# lupa-carrier.net
KiCad netlist of a schematic drawn in EAGLE
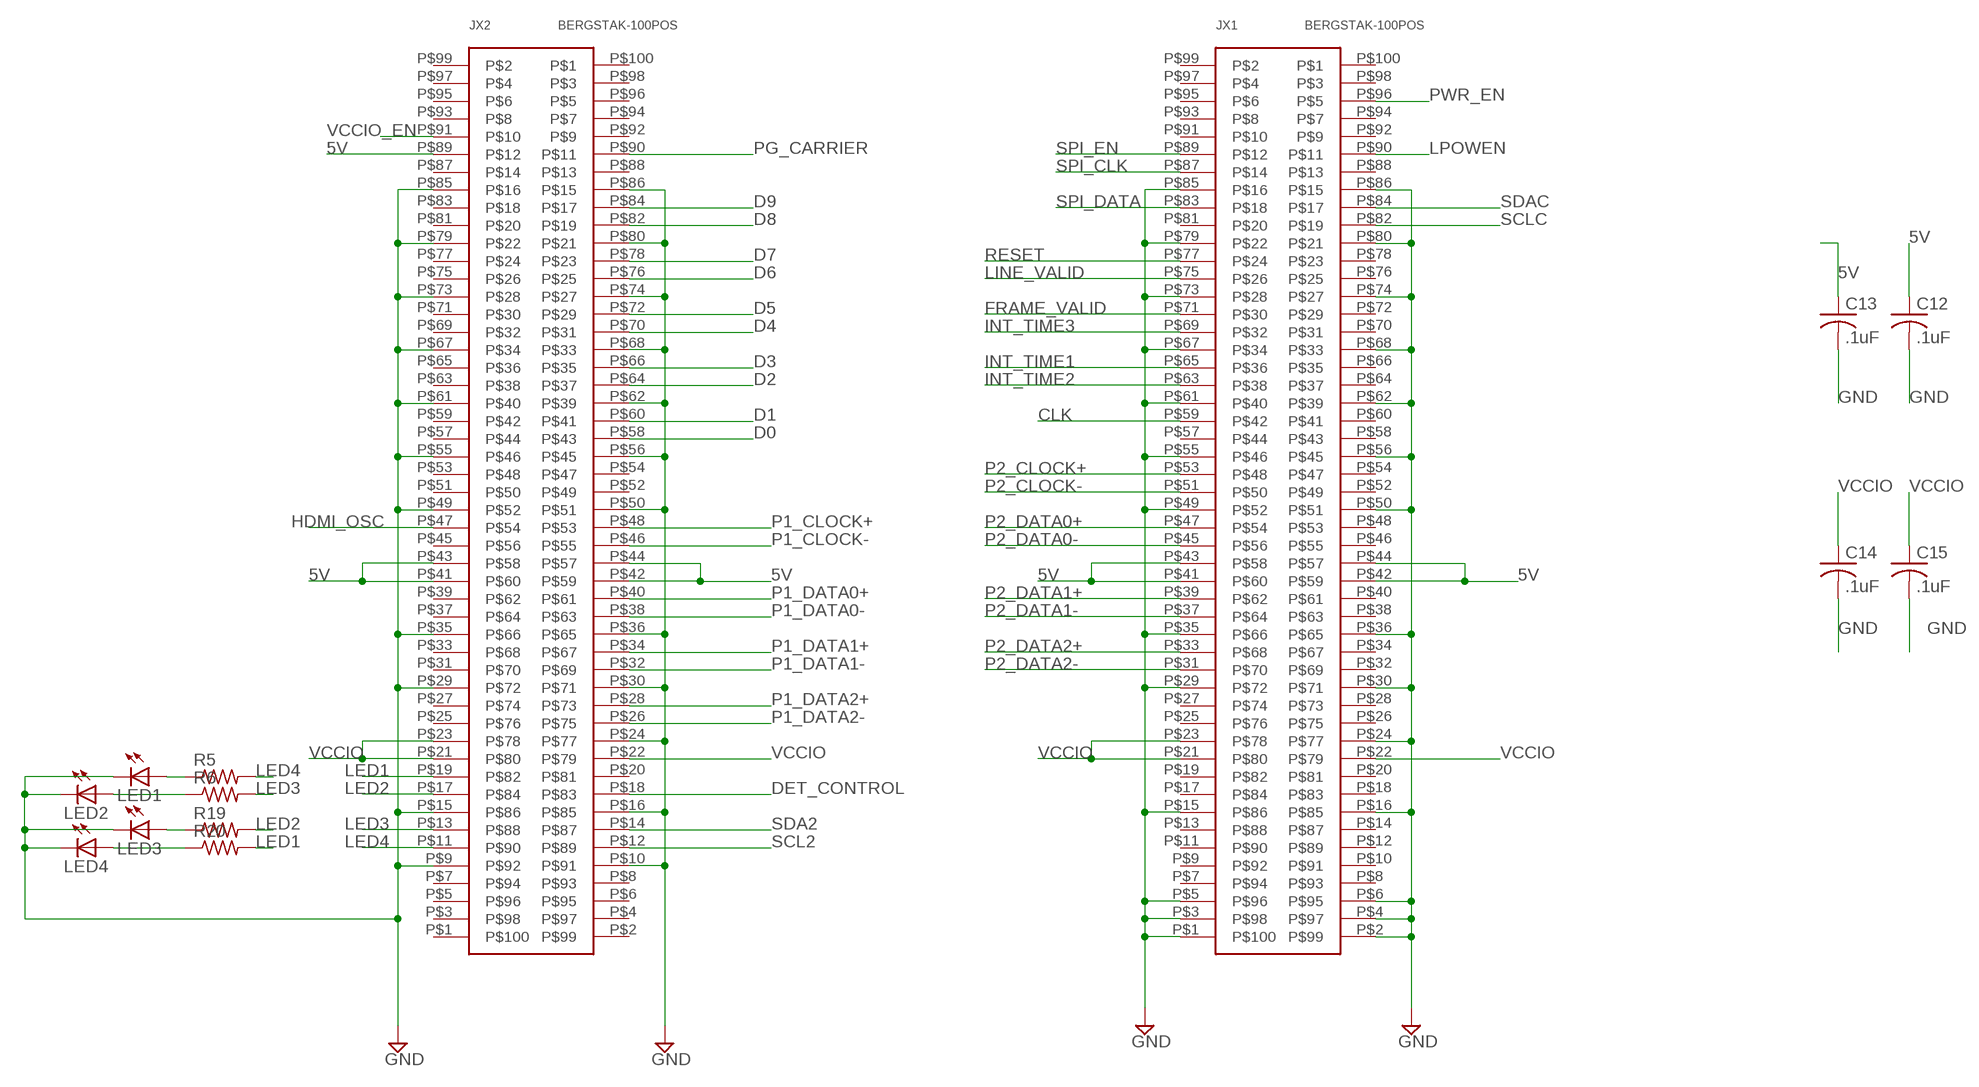
[diagram p0: schematic, sheet 1]
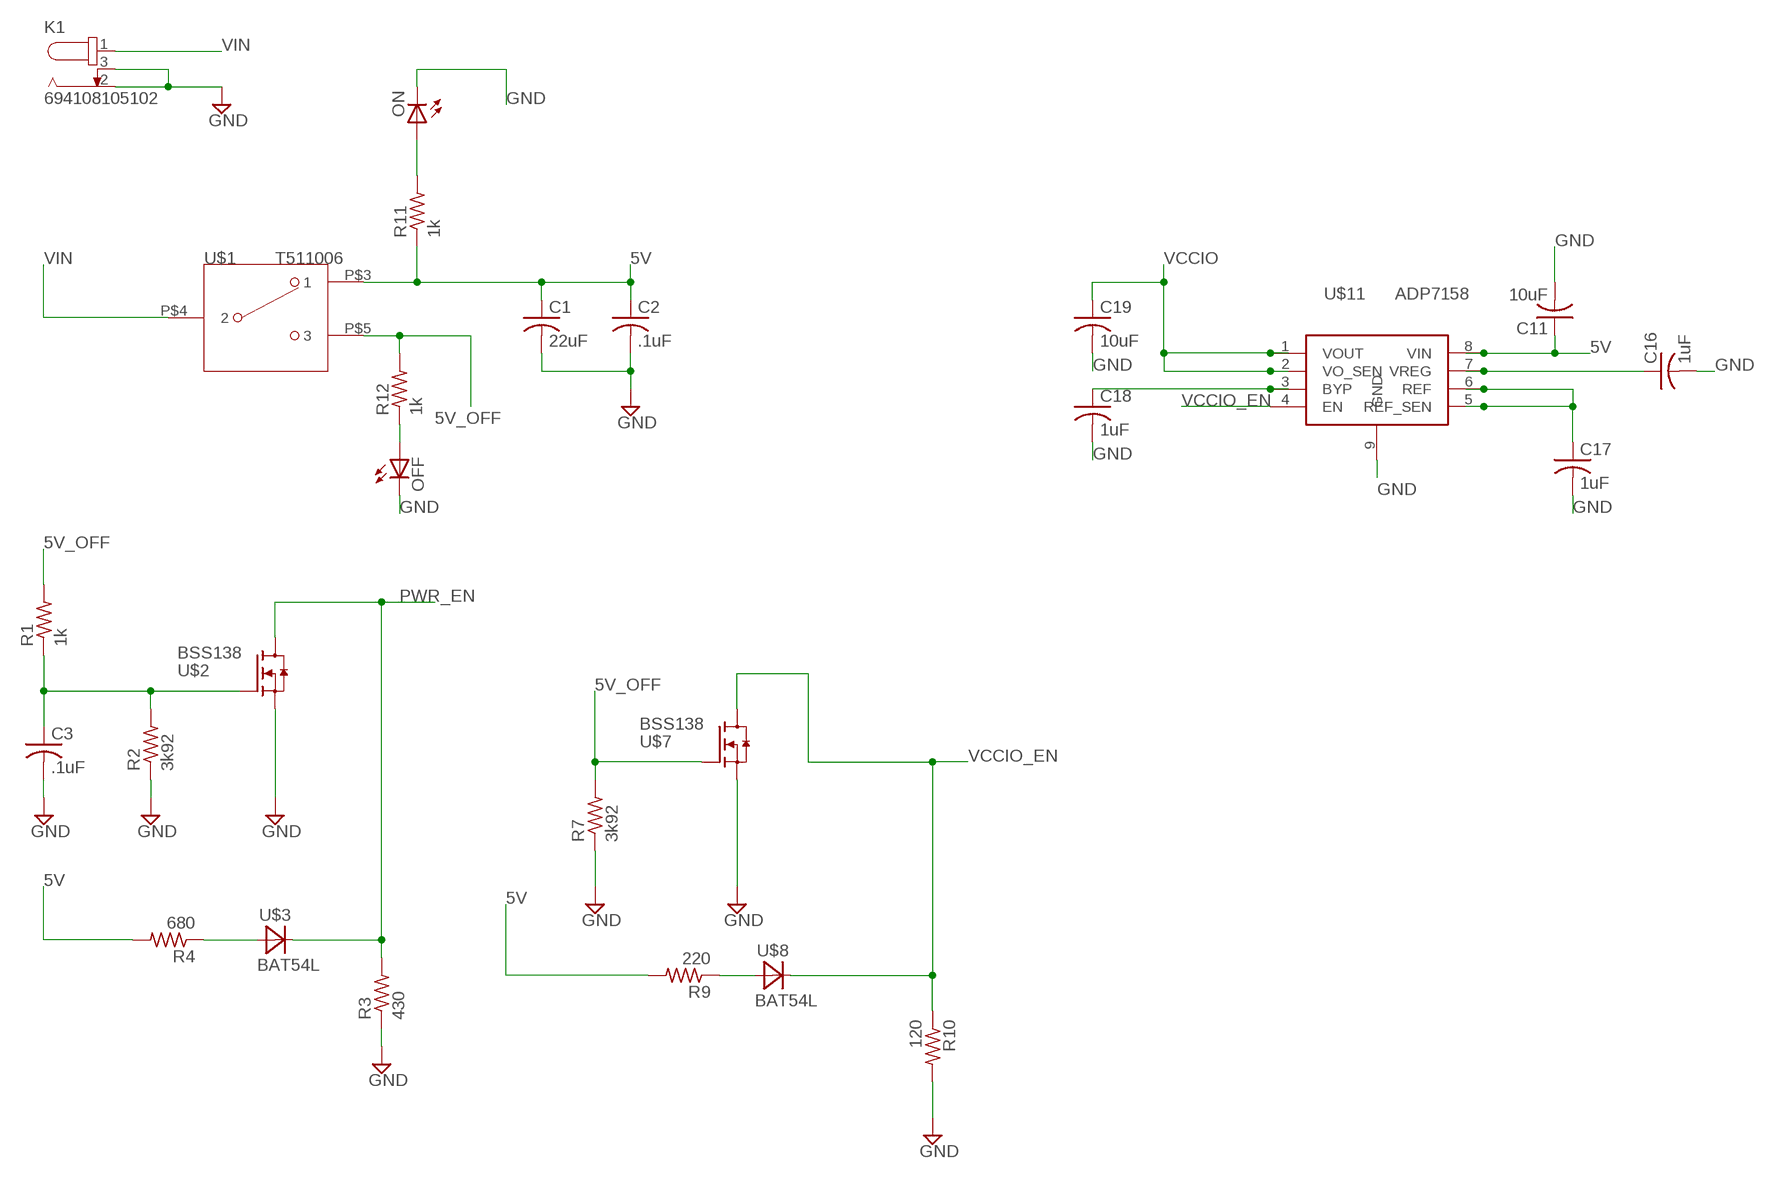
[diagram p1: schematic, sheet 2]
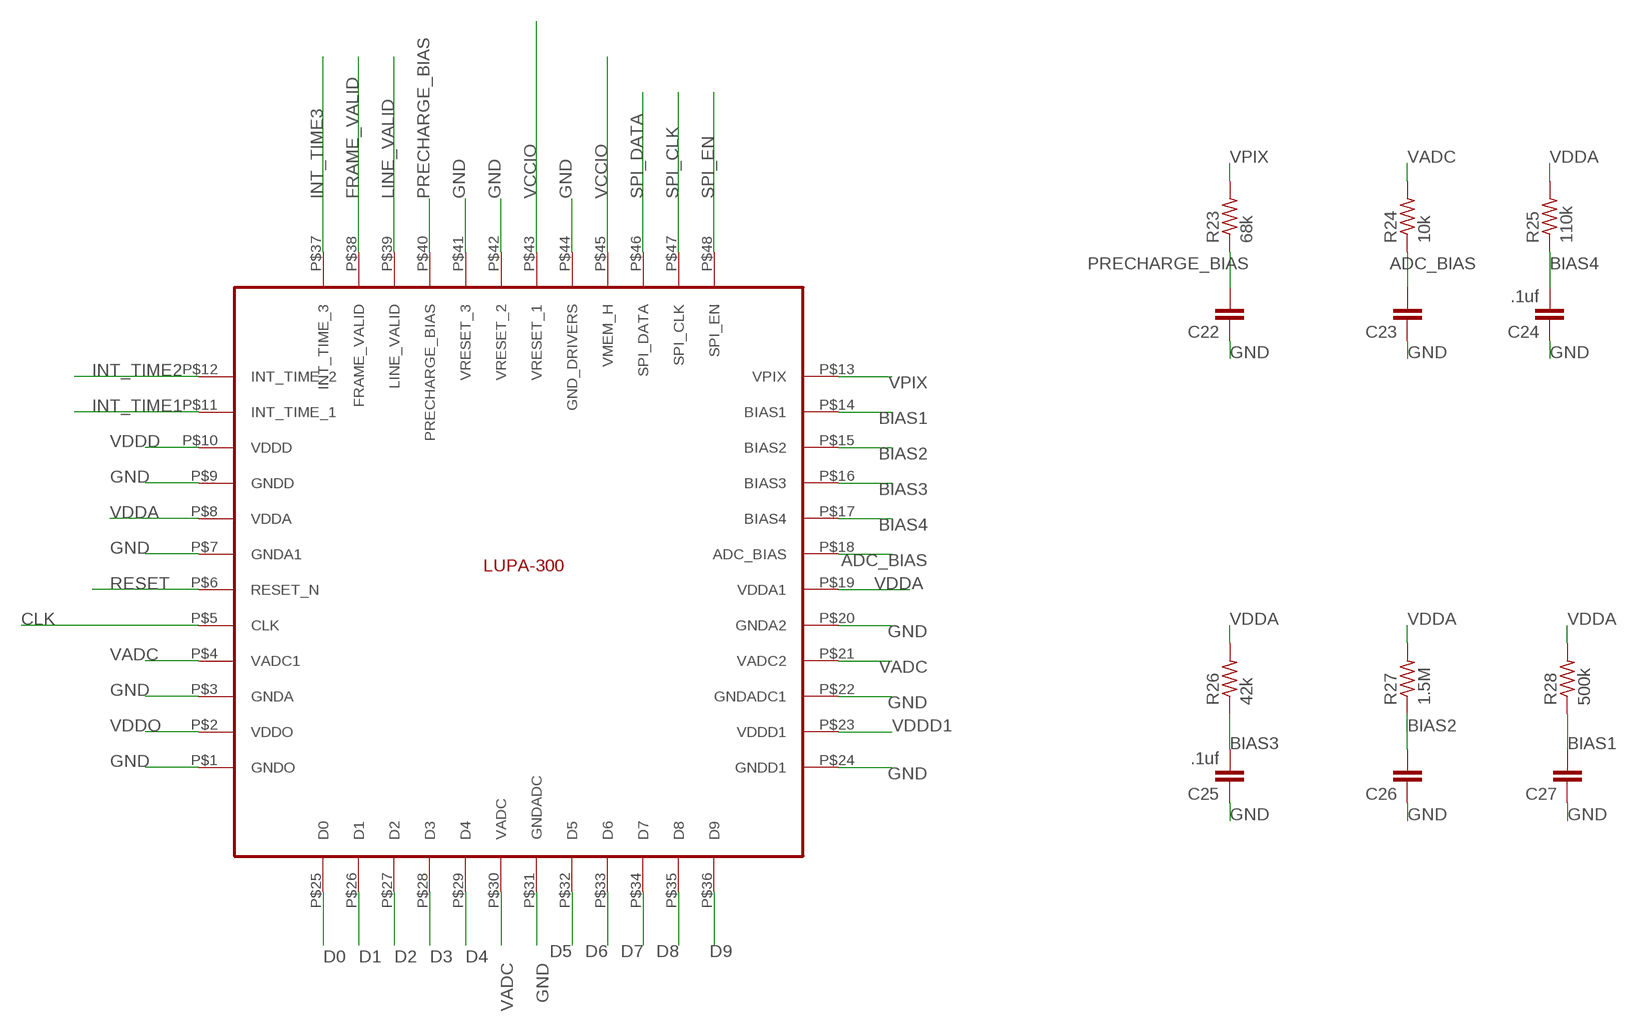
[diagram p2: schematic, sheet 3]
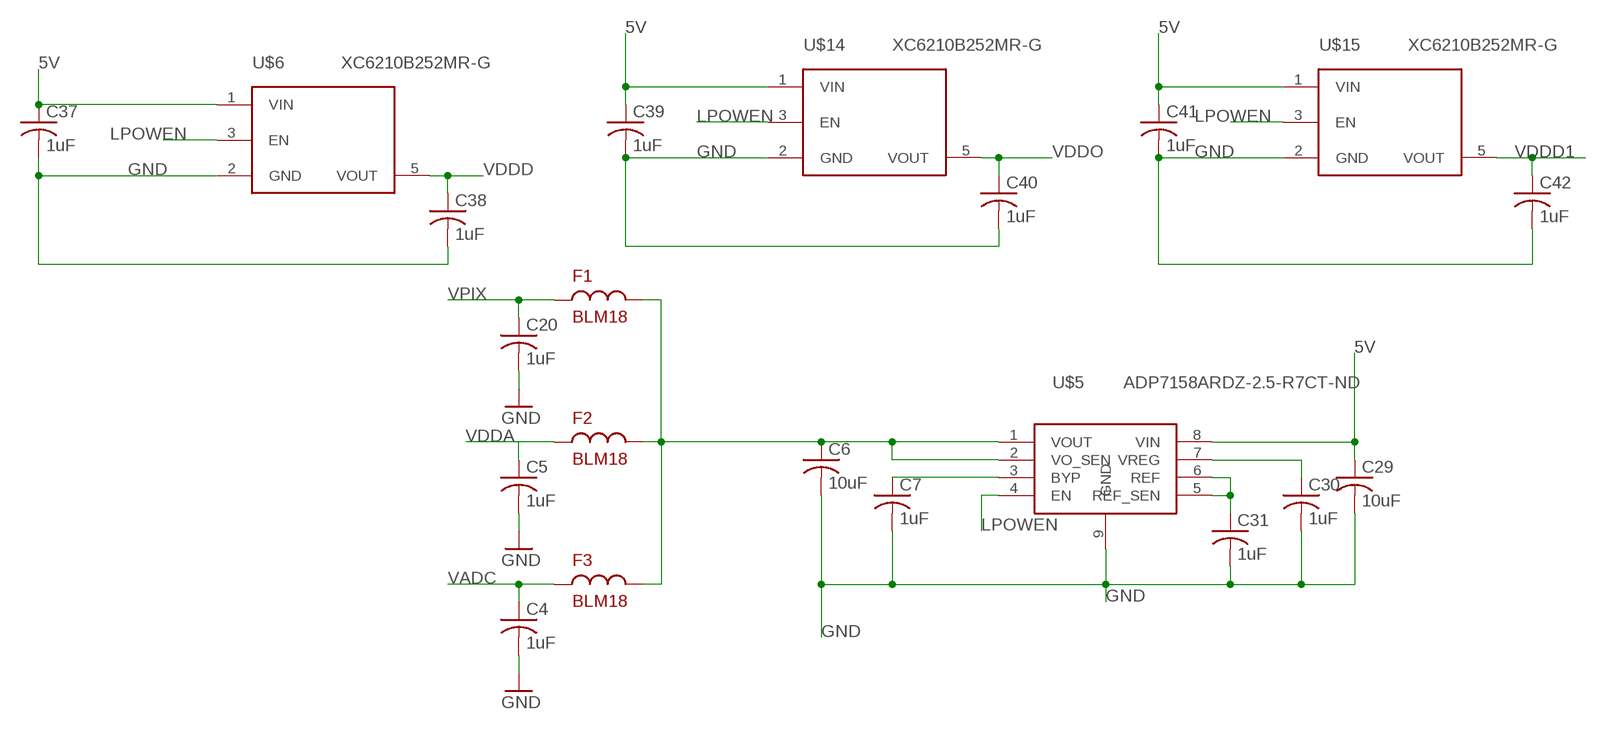
[diagram p3: schematic, sheet 4]
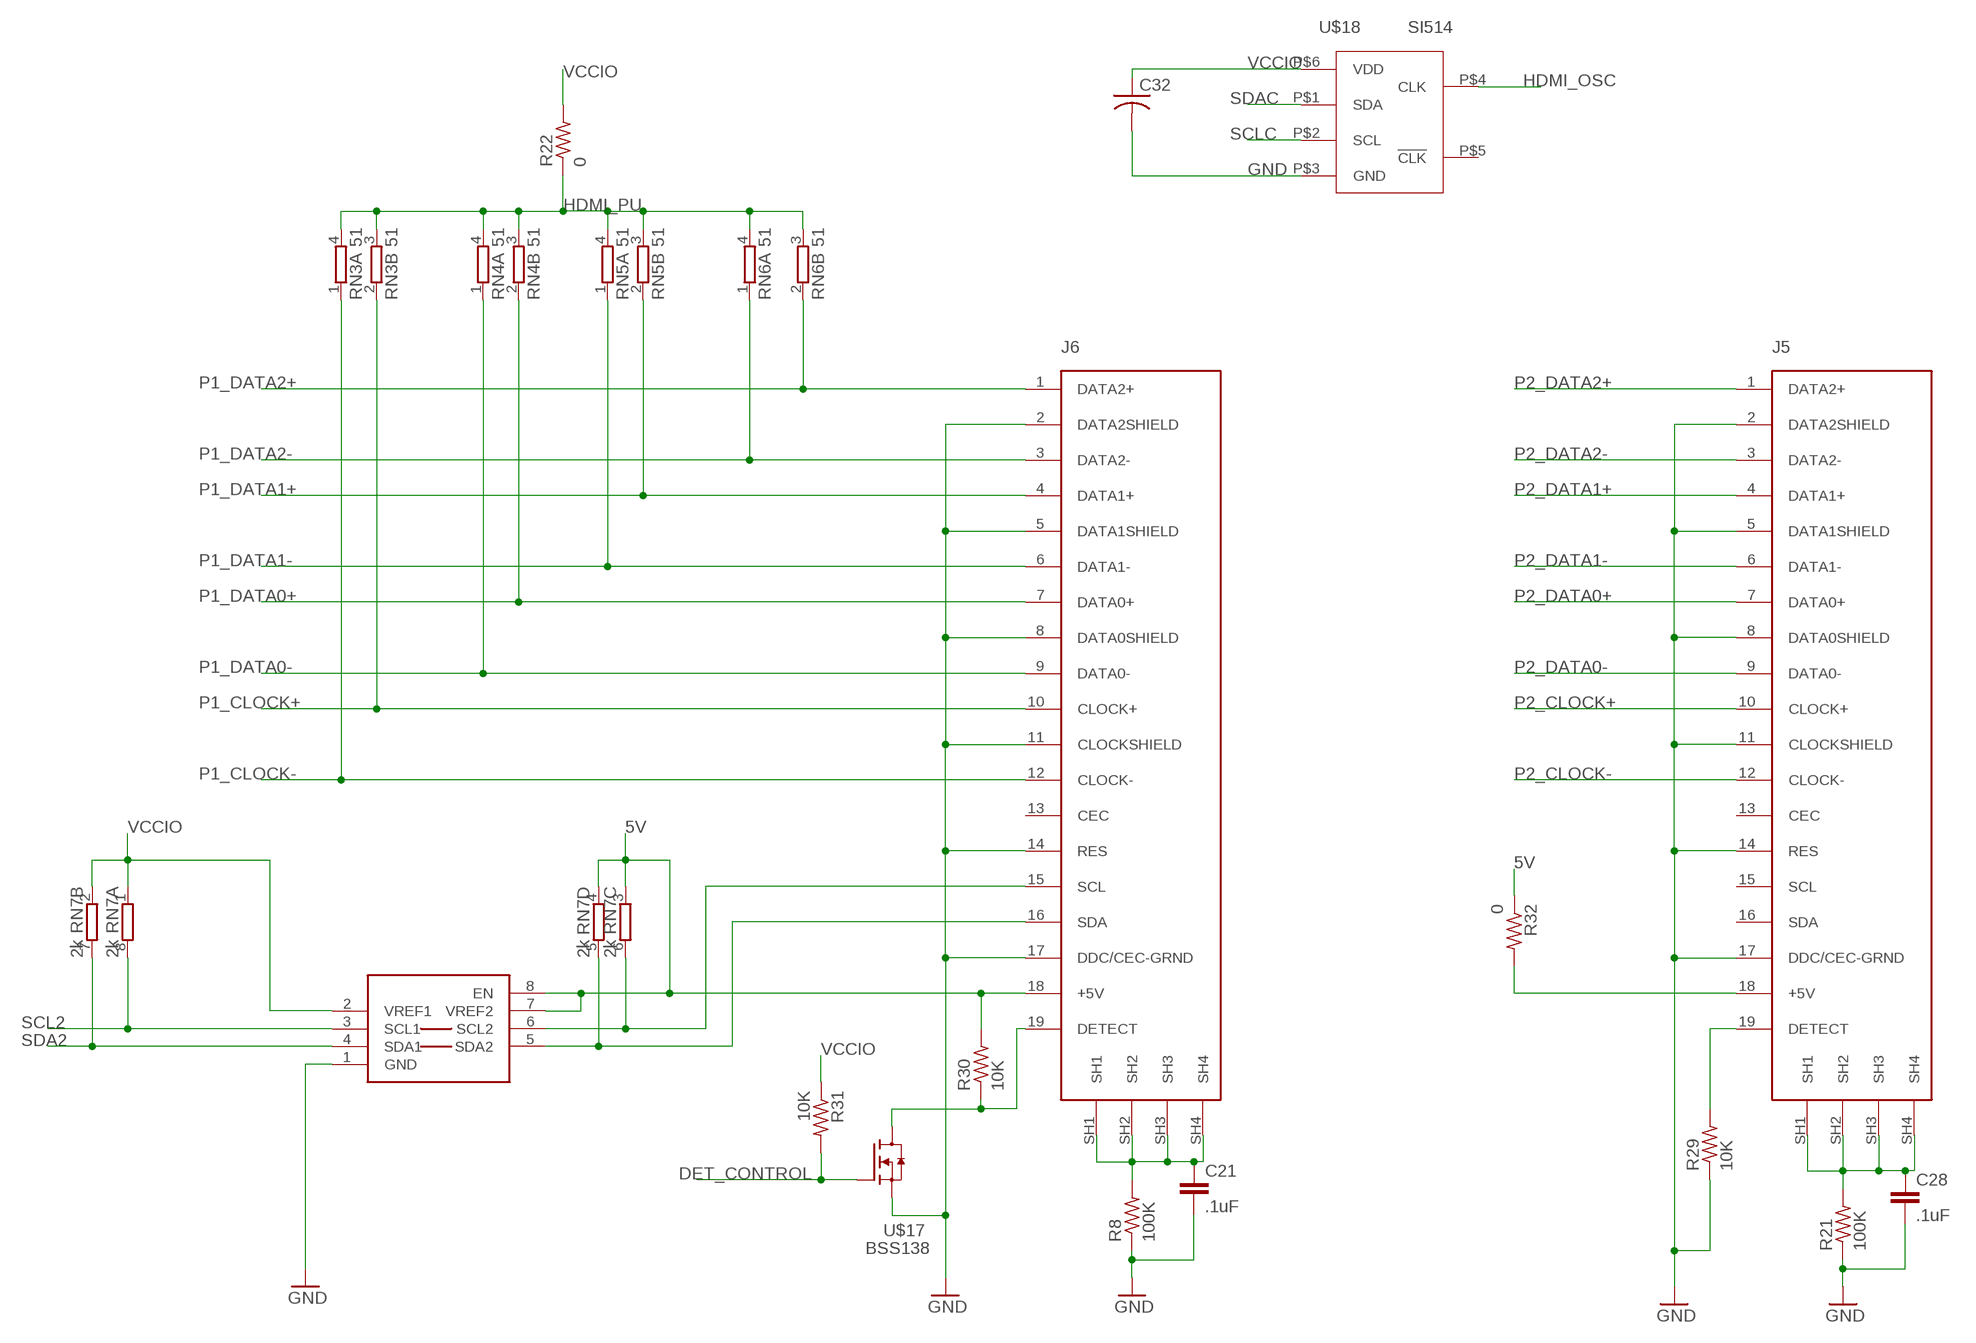
[diagram p4: schematic, sheet 5]

(export (version "E")
  (design (tool "Eeschema 10.0.6"))
  (components
    (comp (ref "C1")
      (value "22uF")
      (footprint "eagle-import:C1206")
      (libsource (lib "eagle-import") (part "C-USC1206"))
    )
    (comp (ref "C2")
      (value ".1uF")
      (footprint "eagle-import:C0603")
      (libsource (lib "eagle-import") (part "C-USC0603"))
    )
    (comp (ref "C3")
      (value ".1uF")
      (footprint "eagle-import:C0603")
      (libsource (lib "eagle-import") (part "C-USC0603"))
    )
    (comp (ref "C11")
      (value "10uF")
      (footprint "eagle-import:C0603")
      (libsource (lib "eagle-import") (part "C-USC0603"))
    )
    (comp (ref "C16")
      (value "1uF")
      (footprint "eagle-import:C0603")
      (libsource (lib "eagle-import") (part "C-USC0603"))
    )
    (comp (ref "C17")
      (value "1uF")
      (footprint "eagle-import:C0603")
      (libsource (lib "eagle-import") (part "C-USC0603"))
    )
    (comp (ref "C18")
      (value "1uF")
      (footprint "eagle-import:C0603")
      (libsource (lib "eagle-import") (part "C-USC0603"))
    )
    (comp (ref "C19")
      (value "10uF")
      (footprint "eagle-import:C0603")
      (libsource (lib "eagle-import") (part "C-USC0603"))
    )
    (comp (ref "K1")
      (value "694108105102")
      (footprint "eagle-import:694108105102")
      (libsource (lib "eagle-import") (part "694108105102"))
    )
    (comp (ref "OFF")
      (value "LEDCHIPLED_0805")
      (footprint "eagle-import:CHIPLED_0805")
      (libsource (lib "eagle-import") (part "LEDCHIPLED_0805"))
    )
    (comp (ref "ON")
      (value "LEDCHIPLED_0805")
      (footprint "eagle-import:CHIPLED_0805")
      (libsource (lib "eagle-import") (part "LEDCHIPLED_0805"))
    )
    (comp (ref "R1")
      (value "1k")
      (footprint "eagle-import:R0603")
      (libsource (lib "eagle-import") (part "rcl_334_R-US_R0603"))
    )
    (comp (ref "R2")
      (value "3k92")
      (footprint "eagle-import:R0603")
      (libsource (lib "eagle-import") (part "rcl_334_R-US_R0603"))
    )
    (comp (ref "R3")
      (value "430")
      (footprint "eagle-import:R0603")
      (libsource (lib "eagle-import") (part "rcl_334_R-US_R0603"))
    )
    (comp (ref "R4")
      (value "680")
      (footprint "eagle-import:R0603")
      (libsource (lib "eagle-import") (part "rcl_334_R-US_R0603"))
    )
    (comp (ref "R7")
      (value "3k92")
      (footprint "eagle-import:R0603")
      (libsource (lib "eagle-import") (part "rcl_334_R-US_R0603"))
    )
    (comp (ref "R9")
      (value "220")
      (footprint "eagle-import:R0603")
      (libsource (lib "eagle-import") (part "rcl_334_R-US_R0603"))
    )
    (comp (ref "R10")
      (value "120")
      (footprint "eagle-import:R0603")
      (libsource (lib "eagle-import") (part "rcl_334_R-US_R0603"))
    )
    (comp (ref "R11")
      (value "1k")
      (footprint "eagle-import:R0603")
      (libsource (lib "eagle-import") (part "rcl_334_R-US_R0603"))
    )
    (comp (ref "R12")
      (value "1k")
      (footprint "eagle-import:R0603")
      (libsource (lib "eagle-import") (part "rcl_334_R-US_R0603"))
    )
    (comp (ref "U$1")
      (value "T511006")
      (footprint "eagle-import:SPDT")
      (libsource (lib "eagle-import") (part "T511006"))
    )
    (comp (ref "U$2")
      (value "BSS138")
      (footprint "eagle-import:SOT23")
      (libsource (lib "eagle-import") (part "BSS138"))
    )
    (comp (ref "U$3")
      (value "BAT54L")
      (footprint "eagle-import:SOT23")
      (libsource (lib "eagle-import") (part "BAT54L"))
    )
    (comp (ref "U$7")
      (value "BSS138")
      (footprint "eagle-import:SOT23")
      (libsource (lib "eagle-import") (part "BSS138"))
    )
    (comp (ref "U$8")
      (value "BAT54L")
      (footprint "eagle-import:SOT23")
      (libsource (lib "eagle-import") (part "BAT54L"))
    )
    (comp (ref "U$11")
      (value "ADP7158")
      (footprint "eagle-import:SO08")
      (libsource (lib "eagle-import") (part "ADP7158"))
    )
    (comp (ref "C22")
      (value "C-EUC0603")
      (footprint "eagle-import:C0603")
      (libsource (lib "eagle-import") (part "rcl_334_C-EUC0603"))
    )
    (comp (ref "C23")
      (value "C-EUC0603")
      (footprint "eagle-import:C0603")
      (libsource (lib "eagle-import") (part "rcl_334_C-EUC0603"))
    )
    (comp (ref "C24")
      (value ".1uf")
      (footprint "eagle-import:C0603")
      (libsource (lib "eagle-import") (part "rcl_334_C-EUC0603"))
    )
    (comp (ref "C25")
      (value ".1uf")
      (footprint "eagle-import:C0603")
      (libsource (lib "eagle-import") (part "rcl_334_C-EUC0603"))
    )
    (comp (ref "C26")
      (value "C-EUC0603")
      (footprint "eagle-import:C0603")
      (libsource (lib "eagle-import") (part "rcl_334_C-EUC0603"))
    )
    (comp (ref "C27")
      (value "C-EUC0603")
      (footprint "eagle-import:C0603")
      (libsource (lib "eagle-import") (part "rcl_334_C-EUC0603"))
    )
    (comp (ref "R23")
      (value "68k")
      (footprint "eagle-import:R0603")
      (libsource (lib "eagle-import") (part "rcl_334_R-US_R0603"))
    )
    (comp (ref "R24")
      (value "10k")
      (footprint "eagle-import:R0603")
      (libsource (lib "eagle-import") (part "rcl_334_R-US_R0603"))
    )
    (comp (ref "R25")
      (value "110k")
      (footprint "eagle-import:R0603")
      (libsource (lib "eagle-import") (part "rcl_334_R-US_R0603"))
    )
    (comp (ref "R26")
      (value "42k")
      (footprint "eagle-import:R0603")
      (libsource (lib "eagle-import") (part "rcl_334_R-US_R0603"))
    )
    (comp (ref "R27")
      (value "1.5M")
      (footprint "eagle-import:R0603")
      (libsource (lib "eagle-import") (part "rcl_334_R-US_R0603"))
    )
    (comp (ref "R28")
      (value "500k")
      (footprint "eagle-import:R0603")
      (libsource (lib "eagle-import") (part "rcl_334_R-US_R0603"))
    )
    (comp (ref "U$4")
      (value "LUPA300")
      (footprint "eagle-import:LUPA300")
      (libsource (lib "eagle-import") (part "LUPA300"))
    )
    (comp (ref "C21")
      (value ".1uF")
      (footprint "eagle-import:C0603K")
      (libsource (lib "eagle-import") (part "C-EUC0603K"))
    )
    (comp (ref "C28")
      (value ".1uF")
      (footprint "eagle-import:C0603K")
      (libsource (lib "eagle-import") (part "C-EUC0603K"))
    )
    (comp (ref "C32")
      (value "C-USC0603")
      (footprint "eagle-import:C0603")
      (libsource (lib "eagle-import") (part "C-USC0603"))
    )
    (comp (ref "J5")
      (value "HDMI-TYPE-A-RECEPTICALFCI10029449")
      (footprint "eagle-import:FCI-HDMI-TYPE-A-RECEPT")
      (libsource (lib "eagle-import") (part "HDMI-TYPE-A-RECEPTICALFCI10029449"))
    )
    (comp (ref "J6")
      (value "HDMI-TYPE-A-RECEPTICALFCI10029449")
      (footprint "eagle-import:FCI-HDMI-TYPE-A-RECEPT")
      (libsource (lib "eagle-import") (part "HDMI-TYPE-A-RECEPTICALFCI10029449"))
    )
    (comp (ref "PCA9306")
      (value "PCA9306")
      (footprint "eagle-import:PSOP-8")
      (libsource (lib "eagle-import") (part "PCA9306"))
    )
    (comp (ref "R8")
      (value "100K")
      (footprint "eagle-import:R0603")
      (libsource (lib "eagle-import") (part "R-US_R0603"))
    )
    (comp (ref "R21")
      (value "100K")
      (footprint "eagle-import:R0603")
      (libsource (lib "eagle-import") (part "R-US_R0603"))
    )
    (comp (ref "R22")
      (value "0")
      (footprint "eagle-import:R0603")
      (libsource (lib "eagle-import") (part "rcl_334_R-US_R0603"))
    )
    (comp (ref "R29")
      (value "10K")
      (footprint "eagle-import:R0603")
      (libsource (lib "eagle-import") (part "R-US_R0603"))
    )
    (comp (ref "R30")
      (value "10K")
      (footprint "eagle-import:R0603")
      (libsource (lib "eagle-import") (part "R-US_R0603"))
    )
    (comp (ref "R31")
      (value "10K")
      (footprint "eagle-import:R0603")
      (libsource (lib "eagle-import") (part "R-US_R0603"))
    )
    (comp (ref "R32")
      (value "0")
      (footprint "eagle-import:R0603")
      (libsource (lib "eagle-import") (part "R-US_R0603"))
    )
    (comp (ref "RN3")
      (value "51")
      (footprint "eagle-import:EXB34V")
      (libsource (lib "eagle-import") (part "2R-NEXB34V"))
    )
    (comp (ref "RN4")
      (value "51")
      (footprint "eagle-import:EXB34V")
      (libsource (lib "eagle-import") (part "2R-NEXB34V"))
    )
    (comp (ref "RN5")
      (value "51")
      (footprint "eagle-import:EXB34V")
      (libsource (lib "eagle-import") (part "2R-NEXB34V"))
    )
    (comp (ref "RN6")
      (value "51")
      (footprint "eagle-import:EXB34V")
      (libsource (lib "eagle-import") (part "2R-NEXB34V"))
    )
    (comp (ref "RN7")
      (value "2k")
      (footprint "eagle-import:0603-ARV")
      (libsource (lib "eagle-import") (part "4R-N0603-ARV"))
    )
    (comp (ref "U$17")
      (value "BSS138")
      (footprint "eagle-import:SOT23")
      (libsource (lib "eagle-import") (part "BSS138"))
    )
    (comp (ref "U$18")
      (value "SI514")
      (footprint "eagle-import:XTAL-6PIN")
      (libsource (lib "eagle-import") (part "SI514"))
    )
    (comp (ref "C12")
      (value ".1uF")
      (footprint "eagle-import:C0603")
      (libsource (lib "eagle-import") (part "C-USC0603"))
    )
    (comp (ref "C13")
      (value ".1uF")
      (footprint "eagle-import:C0603")
      (libsource (lib "eagle-import") (part "C-USC0603"))
    )
    (comp (ref "C14")
      (value ".1uF")
      (footprint "eagle-import:C0603")
      (libsource (lib "eagle-import") (part "C-USC0603"))
    )
    (comp (ref "C15")
      (value ".1uF")
      (footprint "eagle-import:C0603")
      (libsource (lib "eagle-import") (part "C-USC0603"))
    )
    (comp (ref "JX1")
      (value "BERGSTAK-100POS")
      (footprint "eagle-import:BERG100POS")
      (libsource (lib "eagle-import") (part "BERGSTAK-100POS"))
    )
    (comp (ref "JX2")
      (value "BERGSTAK-100POS")
      (footprint "eagle-import:BERG100POS")
      (libsource (lib "eagle-import") (part "BERGSTAK-100POS"))
    )
    (comp (ref "LED1")
      (value "LEDCHIPLED_0805")
      (footprint "eagle-import:CHIPLED_0805")
      (libsource (lib "eagle-import") (part "led_259_LEDCHIPLED_0805"))
    )
    (comp (ref "LED2")
      (value "LEDCHIPLED_0805")
      (footprint "eagle-import:CHIPLED_0805")
      (libsource (lib "eagle-import") (part "led_259_LEDCHIPLED_0805"))
    )
    (comp (ref "LED3")
      (value "LEDCHIPLED_0805")
      (footprint "eagle-import:CHIPLED_0805")
      (libsource (lib "eagle-import") (part "led_259_LEDCHIPLED_0805"))
    )
    (comp (ref "LED4")
      (value "LEDCHIPLED_0805")
      (footprint "eagle-import:CHIPLED_0805")
      (libsource (lib "eagle-import") (part "led_259_LEDCHIPLED_0805"))
    )
    (comp (ref "R5")
      (value "R-US_R0603")
      (footprint "eagle-import:R0603")
      (libsource (lib "eagle-import") (part "resistor_348_R-US_R0603"))
    )
    (comp (ref "R6")
      (value "R-US_R0603")
      (footprint "eagle-import:R0603")
      (libsource (lib "eagle-import") (part "resistor_348_R-US_R0603"))
    )
    (comp (ref "R19")
      (value "R-US_R0603")
      (footprint "eagle-import:R0603")
      (libsource (lib "eagle-import") (part "resistor_348_R-US_R0603"))
    )
    (comp (ref "R20")
      (value "R-US_R0603")
      (footprint "eagle-import:R0603")
      (libsource (lib "eagle-import") (part "resistor_348_R-US_R0603"))
    )
    (comp (ref "C4")
      (value "1uF")
      (footprint "eagle-import:C0603")
      (libsource (lib "eagle-import") (part "C-USC0603"))
    )
    (comp (ref "C5")
      (value "1uF")
      (footprint "eagle-import:C0603")
      (libsource (lib "eagle-import") (part "C-USC0603"))
    )
    (comp (ref "C6")
      (value "10uF")
      (footprint "eagle-import:C0603")
      (libsource (lib "eagle-import") (part "C-USC0603"))
    )
    (comp (ref "C7")
      (value "1uF")
      (footprint "eagle-import:C0603")
      (libsource (lib "eagle-import") (part "C-USC0603"))
    )
    (comp (ref "C20")
      (value "1uF")
      (footprint "eagle-import:C0603")
      (libsource (lib "eagle-import") (part "C-USC0603"))
    )
    (comp (ref "C29")
      (value "10uF")
      (footprint "eagle-import:C0603")
      (libsource (lib "eagle-import") (part "C-USC0603"))
    )
    (comp (ref "C30")
      (value "1uF")
      (footprint "eagle-import:C0603")
      (libsource (lib "eagle-import") (part "C-USC0603"))
    )
    (comp (ref "C31")
      (value "1uF")
      (footprint "eagle-import:C0603")
      (libsource (lib "eagle-import") (part "C-USC0603"))
    )
    (comp (ref "C37")
      (value "1uF")
      (footprint "eagle-import:C0603")
      (libsource (lib "eagle-import") (part "C-USC0603"))
    )
    (comp (ref "C38")
      (value "1uF")
      (footprint "eagle-import:C0603")
      (libsource (lib "eagle-import") (part "C-USC0603"))
    )
    (comp (ref "C39")
      (value "1uF")
      (footprint "eagle-import:C0603")
      (libsource (lib "eagle-import") (part "C-USC0603"))
    )
    (comp (ref "C40")
      (value "1uF")
      (footprint "eagle-import:C0603")
      (libsource (lib "eagle-import") (part "C-USC0603"))
    )
    (comp (ref "C41")
      (value "1uF")
      (footprint "eagle-import:C0603")
      (libsource (lib "eagle-import") (part "C-USC0603"))
    )
    (comp (ref "C42")
      (value "1uF")
      (footprint "eagle-import:C0603")
      (libsource (lib "eagle-import") (part "C-USC0603"))
    )
    (comp (ref "F1")
      (value "BLM18")
      (footprint "eagle-import:C0603K")
      (libsource (lib "eagle-import") (part "BLM18"))
    )
    (comp (ref "F2")
      (value "BLM18")
      (footprint "eagle-import:C0603K")
      (libsource (lib "eagle-import") (part "BLM18"))
    )
    (comp (ref "F3")
      (value "BLM18")
      (footprint "eagle-import:C0603K")
      (libsource (lib "eagle-import") (part "BLM18"))
    )
    (comp (ref "U$5")
      (value "ADP7158ARDZ-2.5-R7CT-ND")
      (footprint "eagle-import:SO08")
      (libsource (lib "eagle-import") (part "ADP7158ARDZ-2.5-R7CT-ND"))
    )
    (comp (ref "U$6")
      (value "XC6210B252MR-G")
      (footprint "eagle-import:SOT25")
      (libsource (lib "eagle-import") (part "XC6210B252MR-G"))
    )
    (comp (ref "U$14")
      (value "XC6210B252MR-G")
      (footprint "eagle-import:SOT25")
      (libsource (lib "eagle-import") (part "XC6210B252MR-G"))
    )
    (comp (ref "U$15")
      (value "XC6210B252MR-G")
      (footprint "eagle-import:SOT25")
      (libsource (lib "eagle-import") (part "XC6210B252MR-G"))
    )
  )
  (nets
    (net (code "1") (name "5V") (class "Default")
      (node (ref "C1") (pin "1") (pinfunction "1_1") (pintype "passive"))
      (node (ref "C11") (pin "1") (pinfunction "1_1") (pintype "passive"))
      (node (ref "C12") (pin "1") (pinfunction "1_1") (pintype "passive"))
      (node (ref "C13") (pin "1") (pinfunction "1_1") (pintype "passive"))
      (node (ref "C2") (pin "1") (pinfunction "1_1") (pintype "passive"))
      (node (ref "C29") (pin "1") (pinfunction "1_1") (pintype "passive"))
      (node (ref "C37") (pin "1") (pinfunction "1_1") (pintype "passive"))
      (node (ref "C39") (pin "1") (pinfunction "1_1") (pintype "passive"))
      (node (ref "C41") (pin "1") (pinfunction "1_1") (pintype "passive"))
      (node (ref "J6") (pin "18") (pinfunction "+5V_18") (pintype "bidirectional"))
      (node (ref "JX1") (pin "P$41") (pinfunction "P$60_P$41") (pintype "bidirectional"))
      (node (ref "JX1") (pin "P$42") (pinfunction "P$59_P$42") (pintype "bidirectional"))
      (node (ref "JX1") (pin "P$43") (pinfunction "P$58_P$43") (pintype "bidirectional"))
      (node (ref "JX1") (pin "P$44") (pinfunction "P$57_P$44") (pintype "bidirectional"))
      (node (ref "JX2") (pin "P$41") (pinfunction "P$60_P$41") (pintype "bidirectional"))
      (node (ref "JX2") (pin "P$42") (pinfunction "P$59_P$42") (pintype "bidirectional"))
      (node (ref "JX2") (pin "P$43") (pinfunction "P$58_P$43") (pintype "bidirectional"))
      (node (ref "JX2") (pin "P$44") (pinfunction "P$57_P$44") (pintype "bidirectional"))
      (node (ref "JX2") (pin "P$89") (pinfunction "P$12_P$89") (pintype "bidirectional"))
      (node (ref "PCA9306") (pin "7") (pinfunction "VREF2_7") (pintype "bidirectional"))
      (node (ref "PCA9306") (pin "8") (pinfunction "EN_8") (pintype "bidirectional"))
      (node (ref "R11") (pin "1") (pinfunction "1_1") (pintype "passive"))
      (node (ref "R30") (pin "2") (pinfunction "2_2") (pintype "passive"))
      (node (ref "R32") (pin "1") (pinfunction "1_1") (pintype "passive"))
      (node (ref "R4") (pin "2") (pinfunction "2_2") (pintype "passive"))
      (node (ref "R9") (pin "2") (pinfunction "2_2") (pintype "passive"))
      (node (ref "RN7") (pin "3") (pinfunction "1_3") (pintype "passive"))
      (node (ref "RN7") (pin "4") (pinfunction "1_4") (pintype "passive"))
      (node (ref "U$1") (pin "P$3") (pinfunction "1_P$3") (pintype "bidirectional"))
      (node (ref "U$11") (pin "8") (pinfunction "VIN_8") (pintype "bidirectional"))
      (node (ref "U$14") (pin "1") (pinfunction "VIN_1") (pintype "bidirectional"))
      (node (ref "U$15") (pin "1") (pinfunction "VIN_1") (pintype "bidirectional"))
      (node (ref "U$5") (pin "8") (pinfunction "VIN_8") (pintype "bidirectional"))
      (node (ref "U$6") (pin "1") (pinfunction "VIN_1") (pintype "bidirectional"))
    )
    (net (code "2") (name "5V_OFF") (class "Default")
      (node (ref "R1") (pin "2") (pinfunction "2_2") (pintype "passive"))
      (node (ref "R12") (pin "2") (pinfunction "2_2") (pintype "passive"))
      (node (ref "R7") (pin "2") (pinfunction "2_2") (pintype "passive"))
      (node (ref "U$1") (pin "P$5") (pinfunction "3_P$5") (pintype "bidirectional"))
      (node (ref "U$7") (pin "1") (pinfunction "G_1") (pintype "passive"))
    )
    (net (code "3") (name "ADC_BIAS") (class "Default")
      (node (ref "C23") (pin "2") (pinfunction "2_2") (pintype "passive"))
      (node (ref "R24") (pin "1") (pinfunction "1_1") (pintype "passive"))
      (node (ref "U$4") (pin "P$18") (pinfunction "ADC_BIAS_P$18") (pintype "bidirectional"))
    )
    (net (code "4") (name "BIAS1") (class "Default")
      (node (ref "C27") (pin "2") (pinfunction "2_2") (pintype "passive"))
      (node (ref "R28") (pin "1") (pinfunction "1_1") (pintype "passive"))
      (node (ref "U$4") (pin "P$14") (pinfunction "BIAS1_P$14") (pintype "bidirectional"))
    )
    (net (code "5") (name "BIAS2") (class "Default")
      (node (ref "C26") (pin "2") (pinfunction "2_2") (pintype "passive"))
      (node (ref "R27") (pin "1") (pinfunction "1_1") (pintype "passive"))
      (node (ref "U$4") (pin "P$15") (pinfunction "BIAS2_P$15") (pintype "bidirectional"))
    )
    (net (code "6") (name "BIAS3") (class "Default")
      (node (ref "C25") (pin "2") (pinfunction "2_2") (pintype "passive"))
      (node (ref "R26") (pin "1") (pinfunction "1_1") (pintype "passive"))
      (node (ref "U$4") (pin "P$16") (pinfunction "BIAS3_P$16") (pintype "bidirectional"))
    )
    (net (code "7") (name "BIAS4") (class "Default")
      (node (ref "C24") (pin "2") (pinfunction "2_2") (pintype "passive"))
      (node (ref "R25") (pin "1") (pinfunction "1_1") (pintype "passive"))
      (node (ref "U$4") (pin "P$17") (pinfunction "BIAS4_P$17") (pintype "bidirectional"))
    )
    (net (code "8") (name "CLK") (class "Default")
      (node (ref "JX1") (pin "P$59") (pinfunction "P$42_P$59") (pintype "bidirectional"))
      (node (ref "U$4") (pin "P$5") (pinfunction "CLK_P$5") (pintype "bidirectional"))
    )
    (net (code "9") (name "D0") (class "Default")
      (node (ref "JX2") (pin "P$58") (pinfunction "P$43_P$58") (pintype "bidirectional"))
      (node (ref "U$4") (pin "P$25") (pinfunction "D0_P$25") (pintype "bidirectional"))
    )
    (net (code "10") (name "D1") (class "Default")
      (node (ref "JX2") (pin "P$60") (pinfunction "P$41_P$60") (pintype "bidirectional"))
      (node (ref "U$4") (pin "P$26") (pinfunction "D1_P$26") (pintype "bidirectional"))
    )
    (net (code "11") (name "D2") (class "Default")
      (node (ref "JX2") (pin "P$64") (pinfunction "P$37_P$64") (pintype "bidirectional"))
      (node (ref "U$4") (pin "P$27") (pinfunction "D2_P$27") (pintype "bidirectional"))
    )
    (net (code "12") (name "D3") (class "Default")
      (node (ref "JX2") (pin "P$66") (pinfunction "P$35_P$66") (pintype "bidirectional"))
      (node (ref "U$4") (pin "P$28") (pinfunction "D3_P$28") (pintype "bidirectional"))
    )
    (net (code "13") (name "D4") (class "Default")
      (node (ref "JX2") (pin "P$70") (pinfunction "P$31_P$70") (pintype "bidirectional"))
      (node (ref "U$4") (pin "P$29") (pinfunction "D4_P$29") (pintype "bidirectional"))
    )
    (net (code "14") (name "D5") (class "Default")
      (node (ref "JX2") (pin "P$72") (pinfunction "P$29_P$72") (pintype "bidirectional"))
      (node (ref "U$4") (pin "P$32") (pinfunction "D5_P$32") (pintype "bidirectional"))
    )
    (net (code "15") (name "D6") (class "Default")
      (node (ref "JX2") (pin "P$76") (pinfunction "P$25_P$76") (pintype "bidirectional"))
      (node (ref "U$4") (pin "P$33") (pinfunction "D6_P$33") (pintype "bidirectional"))
    )
    (net (code "16") (name "D7") (class "Default")
      (node (ref "JX2") (pin "P$78") (pinfunction "P$23_P$78") (pintype "bidirectional"))
      (node (ref "U$4") (pin "P$34") (pinfunction "D7_P$34") (pintype "bidirectional"))
    )
    (net (code "17") (name "D8") (class "Default")
      (node (ref "JX2") (pin "P$82") (pinfunction "P$19_P$82") (pintype "bidirectional"))
      (node (ref "U$4") (pin "P$35") (pinfunction "D8_P$35") (pintype "bidirectional"))
    )
    (net (code "18") (name "D9") (class "Default")
      (node (ref "JX2") (pin "P$84") (pinfunction "P$17_P$84") (pintype "bidirectional"))
      (node (ref "U$4") (pin "P$36") (pinfunction "D9_P$36") (pintype "bidirectional"))
    )
    (net (code "19") (name "DET_CONTROL") (class "Default")
      (node (ref "JX2") (pin "P$18") (pinfunction "P$83_P$18") (pintype "bidirectional"))
      (node (ref "R31") (pin "2") (pinfunction "2_2") (pintype "passive"))
      (node (ref "U$17") (pin "1") (pinfunction "G_1") (pintype "passive"))
    )
    (net (code "20") (name "FRAME_VALID") (class "Default")
      (node (ref "JX1") (pin "P$71") (pinfunction "P$30_P$71") (pintype "bidirectional"))
      (node (ref "U$4") (pin "P$38") (pinfunction "FRAME_VALID_P$38") (pintype "bidirectional"))
    )
    (net (code "21") (name "GND") (class "Default")
      (node (ref "C1") (pin "2") (pinfunction "2_2") (pintype "passive"))
      (node (ref "C11") (pin "2") (pinfunction "2_2") (pintype "passive"))
      (node (ref "C12") (pin "2") (pinfunction "2_2") (pintype "passive"))
      (node (ref "C13") (pin "2") (pinfunction "2_2") (pintype "passive"))
      (node (ref "C14") (pin "2") (pinfunction "2_2") (pintype "passive"))
      (node (ref "C15") (pin "2") (pinfunction "2_2") (pintype "passive"))
      (node (ref "C16") (pin "2") (pinfunction "2_2") (pintype "passive"))
      (node (ref "C17") (pin "2") (pinfunction "2_2") (pintype "passive"))
      (node (ref "C18") (pin "2") (pinfunction "2_2") (pintype "passive"))
      (node (ref "C19") (pin "2") (pinfunction "2_2") (pintype "passive"))
      (node (ref "C2") (pin "2") (pinfunction "2_2") (pintype "passive"))
      (node (ref "C20") (pin "2") (pinfunction "2_2") (pintype "passive"))
      (node (ref "C21") (pin "2") (pinfunction "2_2") (pintype "passive"))
      (node (ref "C22") (pin "1") (pinfunction "1_1") (pintype "passive"))
      (node (ref "C23") (pin "1") (pinfunction "1_1") (pintype "passive"))
      (node (ref "C24") (pin "1") (pinfunction "1_1") (pintype "passive"))
      (node (ref "C25") (pin "1") (pinfunction "1_1") (pintype "passive"))
      (node (ref "C26") (pin "1") (pinfunction "1_1") (pintype "passive"))
      (node (ref "C27") (pin "1") (pinfunction "1_1") (pintype "passive"))
      (node (ref "C28") (pin "2") (pinfunction "2_2") (pintype "passive"))
      (node (ref "C29") (pin "2") (pinfunction "2_2") (pintype "passive"))
      (node (ref "C3") (pin "2") (pinfunction "2_2") (pintype "passive"))
      (node (ref "C30") (pin "2") (pinfunction "2_2") (pintype "passive"))
      (node (ref "C31") (pin "2") (pinfunction "2_2") (pintype "passive"))
      (node (ref "C32") (pin "2") (pinfunction "2_2") (pintype "passive"))
      (node (ref "C37") (pin "2") (pinfunction "2_2") (pintype "passive"))
      (node (ref "C38") (pin "2") (pinfunction "2_2") (pintype "passive"))
      (node (ref "C39") (pin "2") (pinfunction "2_2") (pintype "passive"))
      (node (ref "C4") (pin "2") (pinfunction "2_2") (pintype "passive"))
      (node (ref "C40") (pin "2") (pinfunction "2_2") (pintype "passive"))
      (node (ref "C41") (pin "2") (pinfunction "2_2") (pintype "passive"))
      (node (ref "C42") (pin "2") (pinfunction "2_2") (pintype "passive"))
      (node (ref "C5") (pin "2") (pinfunction "2_2") (pintype "passive"))
      (node (ref "C6") (pin "2") (pinfunction "2_2") (pintype "passive"))
      (node (ref "C7") (pin "2") (pinfunction "2_2") (pintype "passive"))
      (node (ref "J5") (pin "11") (pinfunction "CLOCKSHIELD_11") (pintype "bidirectional"))
      (node (ref "J5") (pin "14") (pinfunction "RES_14") (pintype "bidirectional"))
      (node (ref "J5") (pin "17") (pinfunction "DDC/CEC-GRND_17") (pintype "bidirectional"))
      (node (ref "J5") (pin "2") (pinfunction "DATA2SHIELD_2") (pintype "bidirectional"))
      (node (ref "J5") (pin "5") (pinfunction "DATA1SHIELD_5") (pintype "bidirectional"))
      (node (ref "J5") (pin "8") (pinfunction "DATA0SHIELD_8") (pintype "bidirectional"))
      (node (ref "J6") (pin "11") (pinfunction "CLOCKSHIELD_11") (pintype "bidirectional"))
      (node (ref "J6") (pin "14") (pinfunction "RES_14") (pintype "bidirectional"))
      (node (ref "J6") (pin "17") (pinfunction "DDC/CEC-GRND_17") (pintype "bidirectional"))
      (node (ref "J6") (pin "2") (pinfunction "DATA2SHIELD_2") (pintype "bidirectional"))
      (node (ref "J6") (pin "5") (pinfunction "DATA1SHIELD_5") (pintype "bidirectional"))
      (node (ref "J6") (pin "8") (pinfunction "DATA0SHIELD_8") (pintype "bidirectional"))
      (node (ref "JX1") (pin "P$1") (pinfunction "P$100_P$1") (pintype "bidirectional"))
      (node (ref "JX1") (pin "P$15") (pinfunction "P$86_P$15") (pintype "bidirectional"))
      (node (ref "JX1") (pin "P$16") (pinfunction "P$85_P$16") (pintype "bidirectional"))
      (node (ref "JX1") (pin "P$2") (pinfunction "P$99_P$2") (pintype "bidirectional"))
      (node (ref "JX1") (pin "P$24") (pinfunction "P$77_P$24") (pintype "bidirectional"))
      (node (ref "JX1") (pin "P$29") (pinfunction "P$72_P$29") (pintype "bidirectional"))
      (node (ref "JX1") (pin "P$3") (pinfunction "P$98_P$3") (pintype "bidirectional"))
      (node (ref "JX1") (pin "P$30") (pinfunction "P$71_P$30") (pintype "bidirectional"))
      (node (ref "JX1") (pin "P$35") (pinfunction "P$66_P$35") (pintype "bidirectional"))
      (node (ref "JX1") (pin "P$36") (pinfunction "P$65_P$36") (pintype "bidirectional"))
      (node (ref "JX1") (pin "P$4") (pinfunction "P$97_P$4") (pintype "bidirectional"))
      (node (ref "JX1") (pin "P$49") (pinfunction "P$52_P$49") (pintype "bidirectional"))
      (node (ref "JX1") (pin "P$5") (pinfunction "P$96_P$5") (pintype "bidirectional"))
      (node (ref "JX1") (pin "P$50") (pinfunction "P$51_P$50") (pintype "bidirectional"))
      (node (ref "JX1") (pin "P$55") (pinfunction "P$46_P$55") (pintype "bidirectional"))
      (node (ref "JX1") (pin "P$56") (pinfunction "P$45_P$56") (pintype "bidirectional"))
      (node (ref "JX1") (pin "P$6") (pinfunction "P$95_P$6") (pintype "bidirectional"))
      (node (ref "JX1") (pin "P$61") (pinfunction "P$40_P$61") (pintype "bidirectional"))
      (node (ref "JX1") (pin "P$62") (pinfunction "P$39_P$62") (pintype "bidirectional"))
      (node (ref "JX1") (pin "P$67") (pinfunction "P$34_P$67") (pintype "bidirectional"))
      (node (ref "JX1") (pin "P$68") (pinfunction "P$33_P$68") (pintype "bidirectional"))
      (node (ref "JX1") (pin "P$73") (pinfunction "P$28_P$73") (pintype "bidirectional"))
      (node (ref "JX1") (pin "P$74") (pinfunction "P$27_P$74") (pintype "bidirectional"))
      (node (ref "JX1") (pin "P$79") (pinfunction "P$22_P$79") (pintype "bidirectional"))
      (node (ref "JX1") (pin "P$80") (pinfunction "P$21_P$80") (pintype "bidirectional"))
      (node (ref "JX1") (pin "P$85") (pinfunction "P$16_P$85") (pintype "bidirectional"))
      (node (ref "JX1") (pin "P$86") (pinfunction "P$15_P$86") (pintype "bidirectional"))
      (node (ref "JX2") (pin "P$10") (pinfunction "P$91_P$10") (pintype "bidirectional"))
      (node (ref "JX2") (pin "P$15") (pinfunction "P$86_P$15") (pintype "bidirectional"))
      (node (ref "JX2") (pin "P$16") (pinfunction "P$85_P$16") (pintype "bidirectional"))
      (node (ref "JX2") (pin "P$24") (pinfunction "P$77_P$24") (pintype "bidirectional"))
      (node (ref "JX2") (pin "P$29") (pinfunction "P$72_P$29") (pintype "bidirectional"))
      (node (ref "JX2") (pin "P$30") (pinfunction "P$71_P$30") (pintype "bidirectional"))
      (node (ref "JX2") (pin "P$35") (pinfunction "P$66_P$35") (pintype "bidirectional"))
      (node (ref "JX2") (pin "P$36") (pinfunction "P$65_P$36") (pintype "bidirectional"))
      (node (ref "JX2") (pin "P$49") (pinfunction "P$52_P$49") (pintype "bidirectional"))
      (node (ref "JX2") (pin "P$50") (pinfunction "P$51_P$50") (pintype "bidirectional"))
      (node (ref "JX2") (pin "P$55") (pinfunction "P$46_P$55") (pintype "bidirectional"))
      (node (ref "JX2") (pin "P$56") (pinfunction "P$45_P$56") (pintype "bidirectional"))
      (node (ref "JX2") (pin "P$61") (pinfunction "P$40_P$61") (pintype "bidirectional"))
      (node (ref "JX2") (pin "P$62") (pinfunction "P$39_P$62") (pintype "bidirectional"))
      (node (ref "JX2") (pin "P$67") (pinfunction "P$34_P$67") (pintype "bidirectional"))
      (node (ref "JX2") (pin "P$68") (pinfunction "P$33_P$68") (pintype "bidirectional"))
      (node (ref "JX2") (pin "P$73") (pinfunction "P$28_P$73") (pintype "bidirectional"))
      (node (ref "JX2") (pin "P$74") (pinfunction "P$27_P$74") (pintype "bidirectional"))
      (node (ref "JX2") (pin "P$79") (pinfunction "P$22_P$79") (pintype "bidirectional"))
      (node (ref "JX2") (pin "P$80") (pinfunction "P$21_P$80") (pintype "bidirectional"))
      (node (ref "JX2") (pin "P$85") (pinfunction "P$16_P$85") (pintype "bidirectional"))
      (node (ref "JX2") (pin "P$86") (pinfunction "P$15_P$86") (pintype "bidirectional"))
      (node (ref "JX2") (pin "P$9") (pinfunction "P$92_P$9") (pintype "bidirectional"))
      (node (ref "K1") (pin "2") (pinfunction "2_2") (pintype "passive"))
      (node (ref "K1") (pin "3") (pinfunction "3_3") (pintype "passive"))
      (node (ref "LED1") (pin "C") (pinfunction "C_C") (pintype "passive"))
      (node (ref "LED2") (pin "C") (pinfunction "C_C") (pintype "passive"))
      (node (ref "LED3") (pin "C") (pinfunction "C_C") (pintype "passive"))
      (node (ref "LED4") (pin "C") (pinfunction "C_C") (pintype "passive"))
      (node (ref "OFF") (pin "C") (pinfunction "C_C") (pintype "passive"))
      (node (ref "ON") (pin "C") (pinfunction "C_C") (pintype "passive"))
      (node (ref "PCA9306") (pin "1") (pinfunction "GND_1") (pintype "bidirectional"))
      (node (ref "R10") (pin "2") (pinfunction "2_2") (pintype "passive"))
      (node (ref "R2") (pin "1") (pinfunction "1_1") (pintype "passive"))
      (node (ref "R21") (pin "1") (pinfunction "1_1") (pintype "passive"))
      (node (ref "R29") (pin "1") (pinfunction "1_1") (pintype "passive"))
      (node (ref "R3") (pin "1") (pinfunction "1_1") (pintype "passive"))
      (node (ref "R7") (pin "1") (pinfunction "1_1") (pintype "passive"))
      (node (ref "R8") (pin "1") (pinfunction "1_1") (pintype "passive"))
      (node (ref "U$11") (pin "9") (pinfunction "GND_9") (pintype "bidirectional"))
      (node (ref "U$14") (pin "2") (pinfunction "GND_2") (pintype "bidirectional"))
      (node (ref "U$15") (pin "2") (pinfunction "GND_2") (pintype "bidirectional"))
      (node (ref "U$17") (pin "2") (pinfunction "S_2") (pintype "passive"))
      (node (ref "U$18") (pin "P$3") (pinfunction "GND_P$3") (pintype "bidirectional"))
      (node (ref "U$2") (pin "2") (pinfunction "S_2") (pintype "passive"))
      (node (ref "U$4") (pin "P$1") (pinfunction "GNDO_P$1") (pintype "bidirectional"))
      (node (ref "U$4") (pin "P$20") (pinfunction "GNDA2_P$20") (pintype "bidirectional"))
      (node (ref "U$4") (pin "P$22") (pinfunction "GNDADC1_P$22") (pintype "bidirectional"))
      (node (ref "U$4") (pin "P$24") (pinfunction "GNDD1_P$24") (pintype "bidirectional"))
      (node (ref "U$4") (pin "P$3") (pinfunction "GNDA_P$3") (pintype "bidirectional"))
      (node (ref "U$4") (pin "P$31") (pinfunction "GNDADC_P$31") (pintype "bidirectional"))
      (node (ref "U$4") (pin "P$41") (pinfunction "VRESET_3_P$41") (pintype "bidirectional"))
      (node (ref "U$4") (pin "P$42") (pinfunction "VRESET_2_P$42") (pintype "bidirectional"))
      (node (ref "U$4") (pin "P$44") (pinfunction "GND_DRIVERS_P$44") (pintype "bidirectional"))
      (node (ref "U$4") (pin "P$7") (pinfunction "GNDA1_P$7") (pintype "bidirectional"))
      (node (ref "U$4") (pin "P$9") (pinfunction "GNDD_P$9") (pintype "bidirectional"))
      (node (ref "U$5") (pin "9") (pinfunction "GND_9") (pintype "bidirectional"))
      (node (ref "U$6") (pin "2") (pinfunction "GND_2") (pintype "bidirectional"))
      (node (ref "U$7") (pin "2") (pinfunction "S_2") (pintype "passive"))
    )
    (net (code "22") (name "HDMI_OSC") (class "Default")
      (node (ref "JX2") (pin "P$47") (pinfunction "P$54_P$47") (pintype "bidirectional"))
      (node (ref "U$18") (pin "P$4") (pinfunction "CLK_P$4") (pintype "bidirectional"))
    )
    (net (code "23") (name "HDMI_PU") (class "Default")
      (node (ref "R22") (pin "1") (pinfunction "1_1") (pintype "passive"))
      (node (ref "RN3") (pin "3") (pinfunction "2_3") (pintype "passive"))
      (node (ref "RN3") (pin "4") (pinfunction "2_4") (pintype "passive"))
      (node (ref "RN4") (pin "3") (pinfunction "2_3") (pintype "passive"))
      (node (ref "RN4") (pin "4") (pinfunction "2_4") (pintype "passive"))
      (node (ref "RN5") (pin "3") (pinfunction "2_3") (pintype "passive"))
      (node (ref "RN5") (pin "4") (pinfunction "2_4") (pintype "passive"))
      (node (ref "RN6") (pin "3") (pinfunction "2_3") (pintype "passive"))
      (node (ref "RN6") (pin "4") (pinfunction "2_4") (pintype "passive"))
    )
    (net (code "24") (name "INT_TIME1") (class "Default")
      (node (ref "JX1") (pin "P$65") (pinfunction "P$36_P$65") (pintype "bidirectional"))
      (node (ref "U$4") (pin "P$11") (pinfunction "INT_TIME_1_P$11") (pintype "bidirectional"))
    )
    (net (code "25") (name "INT_TIME2") (class "Default")
      (node (ref "JX1") (pin "P$63") (pinfunction "P$38_P$63") (pintype "bidirectional"))
      (node (ref "U$4") (pin "P$12") (pinfunction "INT_TIME_2_P$12") (pintype "bidirectional"))
    )
    (net (code "26") (name "INT_TIME3") (class "Default")
      (node (ref "JX1") (pin "P$69") (pinfunction "P$32_P$69") (pintype "bidirectional"))
      (node (ref "U$4") (pin "P$37") (pinfunction "INT_TIME_3_P$37") (pintype "bidirectional"))
    )
    (net (code "27") (name "LED1") (class "Default")
      (node (ref "JX2") (pin "P$19") (pinfunction "P$82_P$19") (pintype "bidirectional"))
      (node (ref "R20") (pin "2") (pinfunction "2_2") (pintype "passive"))
    )
    (net (code "28") (name "LED2") (class "Default")
      (node (ref "JX2") (pin "P$17") (pinfunction "P$84_P$17") (pintype "bidirectional"))
      (node (ref "R19") (pin "2") (pinfunction "2_2") (pintype "passive"))
    )
    (net (code "29") (name "LED3") (class "Default")
      (node (ref "JX2") (pin "P$13") (pinfunction "P$88_P$13") (pintype "bidirectional"))
      (node (ref "R6") (pin "2") (pinfunction "2_2") (pintype "passive"))
    )
    (net (code "30") (name "LED4") (class "Default")
      (node (ref "JX2") (pin "P$11") (pinfunction "P$90_P$11") (pintype "bidirectional"))
      (node (ref "R5") (pin "2") (pinfunction "2_2") (pintype "passive"))
    )
    (net (code "31") (name "LINE_VALID") (class "Default")
      (node (ref "JX1") (pin "P$75") (pinfunction "P$26_P$75") (pintype "bidirectional"))
      (node (ref "U$4") (pin "P$39") (pinfunction "LINE_VALID_P$39") (pintype "bidirectional"))
    )
    (net (code "32") (name "LPOWEN") (class "Default")
      (node (ref "JX1") (pin "P$90") (pinfunction "P$11_P$90") (pintype "bidirectional"))
      (node (ref "U$14") (pin "3") (pinfunction "EN_3") (pintype "bidirectional"))
      (node (ref "U$15") (pin "3") (pinfunction "EN_3") (pintype "bidirectional"))
      (node (ref "U$5") (pin "4") (pinfunction "EN_4") (pintype "bidirectional"))
      (node (ref "U$6") (pin "3") (pinfunction "EN_3") (pintype "bidirectional"))
    )
    (net (code "33") (name "Net-(C21-Pad1)") (class "Default")
      (node (ref "C21") (pin "1") (pinfunction "1_1") (pintype "passive"))
      (node (ref "J6") (pin "SH1") (pinfunction "SH1_SH1") (pintype "bidirectional"))
      (node (ref "J6") (pin "SH2") (pinfunction "SH2_SH2") (pintype "bidirectional"))
      (node (ref "J6") (pin "SH3") (pinfunction "SH3_SH3") (pintype "bidirectional"))
      (node (ref "J6") (pin "SH4") (pinfunction "SH4_SH4") (pintype "bidirectional"))
      (node (ref "R8") (pin "2") (pinfunction "2_2") (pintype "passive"))
    )
    (net (code "34") (name "Net-(C28-Pad1)") (class "Default")
      (node (ref "C28") (pin "1") (pinfunction "1_1") (pintype "passive"))
      (node (ref "J5") (pin "SH1") (pinfunction "SH1_SH1") (pintype "bidirectional"))
      (node (ref "J5") (pin "SH2") (pinfunction "SH2_SH2") (pintype "bidirectional"))
      (node (ref "J5") (pin "SH3") (pinfunction "SH3_SH3") (pintype "bidirectional"))
      (node (ref "J5") (pin "SH4") (pinfunction "SH4_SH4") (pintype "bidirectional"))
      (node (ref "R21") (pin "2") (pinfunction "2_2") (pintype "passive"))
    )
    (net (code "35") (name "Net-(J5-+5V)") (class "Default")
      (node (ref "J5") (pin "18") (pinfunction "+5V_18") (pintype "bidirectional"))
      (node (ref "R32") (pin "2") (pinfunction "2_2") (pintype "passive"))
    )
    (net (code "36") (name "Net-(J5-DETECT)") (class "Default")
      (node (ref "J5") (pin "19") (pinfunction "DETECT_19") (pintype "bidirectional"))
      (node (ref "R29") (pin "2") (pinfunction "2_2") (pintype "passive"))
    )
    (net (code "37") (name "Net-(J6-DETECT)") (class "Default")
      (node (ref "J6") (pin "19") (pinfunction "DETECT_19") (pintype "bidirectional"))
      (node (ref "R30") (pin "1") (pinfunction "1_1") (pintype "passive"))
      (node (ref "U$17") (pin "3") (pinfunction "D_3") (pintype "passive"))
    )
    (net (code "38") (name "Net-(J6-SCL)") (class "Default")
      (node (ref "J6") (pin "15") (pinfunction "SCL_15") (pintype "bidirectional"))
      (node (ref "PCA9306") (pin "6") (pinfunction "SCL2_6") (pintype "bidirectional"))
      (node (ref "RN7") (pin "6") (pinfunction "2_6") (pintype "passive"))
    )
    (net (code "39") (name "Net-(J6-SDA)") (class "Default")
      (node (ref "J6") (pin "16") (pinfunction "SDA_16") (pintype "bidirectional"))
      (node (ref "PCA9306") (pin "5") (pinfunction "SDA2_5") (pintype "bidirectional"))
      (node (ref "RN7") (pin "5") (pinfunction "2_5") (pintype "passive"))
    )
    (net (code "40") (name "Net-(LED1-PadA)") (class "Default")
      (node (ref "LED1") (pin "A") (pinfunction "A_A") (pintype "passive"))
      (node (ref "R5") (pin "1") (pinfunction "1_1") (pintype "passive"))
    )
    (net (code "41") (name "Net-(LED2-PadA)") (class "Default")
      (node (ref "LED2") (pin "A") (pinfunction "A_A") (pintype "passive"))
      (node (ref "R6") (pin "1") (pinfunction "1_1") (pintype "passive"))
    )
    (net (code "42") (name "Net-(LED3-PadA)") (class "Default")
      (node (ref "LED3") (pin "A") (pinfunction "A_A") (pintype "passive"))
      (node (ref "R19") (pin "1") (pinfunction "1_1") (pintype "passive"))
    )
    (net (code "43") (name "Net-(LED4-PadA)") (class "Default")
      (node (ref "LED4") (pin "A") (pinfunction "A_A") (pintype "passive"))
      (node (ref "R20") (pin "1") (pinfunction "1_1") (pintype "passive"))
    )
    (net (code "44") (name "Net-(OFF-PadA)") (class "Default")
      (node (ref "OFF") (pin "A") (pinfunction "A_A") (pintype "passive"))
      (node (ref "R12") (pin "1") (pinfunction "1_1") (pintype "passive"))
    )
    (net (code "45") (name "Net-(ON-PadA)") (class "Default")
      (node (ref "ON") (pin "A") (pinfunction "A_A") (pintype "passive"))
      (node (ref "R11") (pin "2") (pinfunction "2_2") (pintype "passive"))
    )
    (net (code "46") (name "Net-(U$2-G)") (class "Default")
      (node (ref "C3") (pin "1") (pinfunction "1_1") (pintype "passive"))
      (node (ref "R1") (pin "1") (pinfunction "1_1") (pintype "passive"))
      (node (ref "R2") (pin "2") (pinfunction "2_2") (pintype "passive"))
      (node (ref "U$2") (pin "1") (pinfunction "G_1") (pintype "passive"))
    )
    (net (code "47") (name "Net-(U$3-A)") (class "Default")
      (node (ref "R4") (pin "1") (pinfunction "1_1") (pintype "passive"))
      (node (ref "U$3") (pin "1") (pinfunction "A_1") (pintype "passive"))
    )
    (net (code "48") (name "Net-(U$5-BYP)") (class "Default")
      (node (ref "C7") (pin "1") (pinfunction "1_1") (pintype "passive"))
      (node (ref "U$5") (pin "3") (pinfunction "BYP_3") (pintype "bidirectional"))
    )
    (net (code "49") (name "Net-(U$5-REF)") (class "Default")
      (node (ref "C31") (pin "1") (pinfunction "1_1") (pintype "passive"))
      (node (ref "U$5") (pin "5") (pinfunction "REF_SEN_5") (pintype "bidirectional"))
      (node (ref "U$5") (pin "6") (pinfunction "REF_6") (pintype "bidirectional"))
    )
    (net (code "50") (name "Net-(U$5-VOUT)") (class "Default")
      (node (ref "C6") (pin "1") (pinfunction "1_1") (pintype "passive"))
      (node (ref "F1") (pin "2") (pinfunction "2_2") (pintype "passive"))
      (node (ref "F2") (pin "2") (pinfunction "2_2") (pintype "passive"))
      (node (ref "F3") (pin "2") (pinfunction "2_2") (pintype "passive"))
      (node (ref "U$5") (pin "1") (pinfunction "VOUT_1") (pintype "bidirectional"))
      (node (ref "U$5") (pin "2") (pinfunction "VO_SEN_2") (pintype "bidirectional"))
    )
    (net (code "51") (name "Net-(U$5-VREG)") (class "Default")
      (node (ref "C30") (pin "1") (pinfunction "1_1") (pintype "passive"))
      (node (ref "U$5") (pin "7") (pinfunction "VREG_7") (pintype "bidirectional"))
    )
    (net (code "52") (name "Net-(U$8-A)") (class "Default")
      (node (ref "R9") (pin "1") (pinfunction "1_1") (pintype "passive"))
      (node (ref "U$8") (pin "1") (pinfunction "A_1") (pintype "passive"))
    )
    (net (code "53") (name "Net-(U$11-BYP)") (class "Default")
      (node (ref "C18") (pin "1") (pinfunction "1_1") (pintype "passive"))
      (node (ref "U$11") (pin "3") (pinfunction "BYP_3") (pintype "bidirectional"))
    )
    (net (code "54") (name "Net-(U$11-REF)") (class "Default")
      (node (ref "C17") (pin "1") (pinfunction "1_1") (pintype "passive"))
      (node (ref "U$11") (pin "5") (pinfunction "REF_SEN_5") (pintype "bidirectional"))
      (node (ref "U$11") (pin "6") (pinfunction "REF_6") (pintype "bidirectional"))
    )
    (net (code "55") (name "Net-(U$11-VREG)") (class "Default")
      (node (ref "C16") (pin "1") (pinfunction "1_1") (pintype "passive"))
      (node (ref "U$11") (pin "7") (pinfunction "VREG_7") (pintype "bidirectional"))
    )
    (net (code "56") (name "P1_CLOCK+") (class "Default")
      (node (ref "J6") (pin "10") (pinfunction "CLOCK+_10") (pintype "bidirectional"))
      (node (ref "JX2") (pin "P$48") (pinfunction "P$53_P$48") (pintype "bidirectional"))
      (node (ref "RN3") (pin "2") (pinfunction "1_2") (pintype "passive"))
    )
    (net (code "57") (name "P1_CLOCK-") (class "Default")
      (node (ref "J6") (pin "12") (pinfunction "CLOCK-_12") (pintype "bidirectional"))
      (node (ref "JX2") (pin "P$46") (pinfunction "P$55_P$46") (pintype "bidirectional"))
      (node (ref "RN3") (pin "1") (pinfunction "1_1") (pintype "passive"))
    )
    (net (code "58") (name "P1_DATA0+") (class "Default")
      (node (ref "J6") (pin "7") (pinfunction "DATA0+_7") (pintype "bidirectional"))
      (node (ref "JX2") (pin "P$40") (pinfunction "P$61_P$40") (pintype "bidirectional"))
      (node (ref "RN4") (pin "2") (pinfunction "1_2") (pintype "passive"))
    )
    (net (code "59") (name "P1_DATA0-") (class "Default")
      (node (ref "J6") (pin "9") (pinfunction "DATA0-_9") (pintype "bidirectional"))
      (node (ref "JX2") (pin "P$38") (pinfunction "P$63_P$38") (pintype "bidirectional"))
      (node (ref "RN4") (pin "1") (pinfunction "1_1") (pintype "passive"))
    )
    (net (code "60") (name "P1_DATA1+") (class "Default")
      (node (ref "J6") (pin "4") (pinfunction "DATA1+_4") (pintype "bidirectional"))
      (node (ref "JX2") (pin "P$34") (pinfunction "P$67_P$34") (pintype "bidirectional"))
      (node (ref "RN5") (pin "2") (pinfunction "1_2") (pintype "passive"))
    )
    (net (code "61") (name "P1_DATA1-") (class "Default")
      (node (ref "J6") (pin "6") (pinfunction "DATA1-_6") (pintype "bidirectional"))
      (node (ref "JX2") (pin "P$32") (pinfunction "P$69_P$32") (pintype "bidirectional"))
      (node (ref "RN5") (pin "1") (pinfunction "1_1") (pintype "passive"))
    )
    (net (code "62") (name "P1_DATA2+") (class "Default")
      (node (ref "J6") (pin "1") (pinfunction "DATA2+_1") (pintype "bidirectional"))
      (node (ref "JX2") (pin "P$28") (pinfunction "P$73_P$28") (pintype "bidirectional"))
      (node (ref "RN6") (pin "2") (pinfunction "1_2") (pintype "passive"))
    )
    (net (code "63") (name "P1_DATA2-") (class "Default")
      (node (ref "J6") (pin "3") (pinfunction "DATA2-_3") (pintype "bidirectional"))
      (node (ref "JX2") (pin "P$26") (pinfunction "P$75_P$26") (pintype "bidirectional"))
      (node (ref "RN6") (pin "1") (pinfunction "1_1") (pintype "passive"))
    )
    (net (code "64") (name "P2_CLOCK+") (class "Default")
      (node (ref "J5") (pin "10") (pinfunction "CLOCK+_10") (pintype "bidirectional"))
      (node (ref "JX1") (pin "P$53") (pinfunction "P$48_P$53") (pintype "bidirectional"))
    )
    (net (code "65") (name "P2_CLOCK-") (class "Default")
      (node (ref "J5") (pin "12") (pinfunction "CLOCK-_12") (pintype "bidirectional"))
      (node (ref "JX1") (pin "P$51") (pinfunction "P$50_P$51") (pintype "bidirectional"))
    )
    (net (code "66") (name "P2_DATA0+") (class "Default")
      (node (ref "J5") (pin "7") (pinfunction "DATA0+_7") (pintype "bidirectional"))
      (node (ref "JX1") (pin "P$47") (pinfunction "P$54_P$47") (pintype "bidirectional"))
    )
    (net (code "67") (name "P2_DATA0-") (class "Default")
      (node (ref "J5") (pin "9") (pinfunction "DATA0-_9") (pintype "bidirectional"))
      (node (ref "JX1") (pin "P$45") (pinfunction "P$56_P$45") (pintype "bidirectional"))
    )
    (net (code "68") (name "P2_DATA1+") (class "Default")
      (node (ref "J5") (pin "4") (pinfunction "DATA1+_4") (pintype "bidirectional"))
      (node (ref "JX1") (pin "P$39") (pinfunction "P$62_P$39") (pintype "bidirectional"))
    )
    (net (code "69") (name "P2_DATA1-") (class "Default")
      (node (ref "J5") (pin "6") (pinfunction "DATA1-_6") (pintype "bidirectional"))
      (node (ref "JX1") (pin "P$37") (pinfunction "P$64_P$37") (pintype "bidirectional"))
    )
    (net (code "70") (name "P2_DATA2+") (class "Default")
      (node (ref "J5") (pin "1") (pinfunction "DATA2+_1") (pintype "bidirectional"))
      (node (ref "JX1") (pin "P$33") (pinfunction "P$68_P$33") (pintype "bidirectional"))
    )
    (net (code "71") (name "P2_DATA2-") (class "Default")
      (node (ref "J5") (pin "3") (pinfunction "DATA2-_3") (pintype "bidirectional"))
      (node (ref "JX1") (pin "P$31") (pinfunction "P$70_P$31") (pintype "bidirectional"))
    )
    (net (code "72") (name "PG_CARRIER") (class "Default")
      (node (ref "JX2") (pin "P$90") (pinfunction "P$11_P$90") (pintype "bidirectional"))
    )
    (net (code "73") (name "PRECHARGE_BIAS") (class "Default")
      (node (ref "C22") (pin "2") (pinfunction "2_2") (pintype "passive"))
      (node (ref "R23") (pin "1") (pinfunction "1_1") (pintype "passive"))
      (node (ref "U$4") (pin "P$40") (pinfunction "PRECHARGE_BIAS_P$40") (pintype "bidirectional"))
    )
    (net (code "74") (name "PWR_EN") (class "Default")
      (node (ref "JX1") (pin "P$96") (pinfunction "P$5_P$96") (pintype "bidirectional"))
      (node (ref "R3") (pin "2") (pinfunction "2_2") (pintype "passive"))
      (node (ref "U$2") (pin "3") (pinfunction "D_3") (pintype "passive"))
      (node (ref "U$3") (pin "3") (pinfunction "C_3") (pintype "passive"))
    )
    (net (code "75") (name "RESET") (class "Default")
      (node (ref "JX1") (pin "P$77") (pinfunction "P$24_P$77") (pintype "bidirectional"))
      (node (ref "U$4") (pin "P$6") (pinfunction "RESET_N_P$6") (pintype "bidirectional"))
    )
    (net (code "76") (name "SCL2") (class "Default")
      (node (ref "JX2") (pin "P$12") (pinfunction "P$89_P$12") (pintype "bidirectional"))
      (node (ref "PCA9306") (pin "3") (pinfunction "SCL1_3") (pintype "bidirectional"))
      (node (ref "RN7") (pin "8") (pinfunction "2_8") (pintype "passive"))
    )
    (net (code "77") (name "SCLC") (class "Default")
      (node (ref "JX1") (pin "P$82") (pinfunction "P$19_P$82") (pintype "bidirectional"))
      (node (ref "U$18") (pin "P$2") (pinfunction "SCL_P$2") (pintype "bidirectional"))
    )
    (net (code "78") (name "SDA2") (class "Default")
      (node (ref "JX2") (pin "P$14") (pinfunction "P$87_P$14") (pintype "bidirectional"))
      (node (ref "PCA9306") (pin "4") (pinfunction "SDA1_4") (pintype "bidirectional"))
      (node (ref "RN7") (pin "7") (pinfunction "2_7") (pintype "passive"))
    )
    (net (code "79") (name "SDAC") (class "Default")
      (node (ref "JX1") (pin "P$84") (pinfunction "P$17_P$84") (pintype "bidirectional"))
      (node (ref "U$18") (pin "P$1") (pinfunction "SDA_P$1") (pintype "bidirectional"))
    )
    (net (code "80") (name "SPI_CLK") (class "Default")
      (node (ref "JX1") (pin "P$87") (pinfunction "P$14_P$87") (pintype "bidirectional"))
      (node (ref "U$4") (pin "P$47") (pinfunction "SPI_CLK_P$47") (pintype "bidirectional"))
    )
    (net (code "81") (name "SPI_DATA") (class "Default")
      (node (ref "JX1") (pin "P$83") (pinfunction "P$18_P$83") (pintype "bidirectional"))
      (node (ref "U$4") (pin "P$46") (pinfunction "SPI_DATA_P$46") (pintype "bidirectional"))
    )
    (net (code "82") (name "SPI_EN") (class "Default")
      (node (ref "JX1") (pin "P$89") (pinfunction "P$12_P$89") (pintype "bidirectional"))
      (node (ref "U$4") (pin "P$48") (pinfunction "SPI_EN_P$48") (pintype "bidirectional"))
    )
    (net (code "83") (name "VADC") (class "Default")
      (node (ref "C4") (pin "1") (pinfunction "1_1") (pintype "passive"))
      (node (ref "F3") (pin "1") (pinfunction "1_1") (pintype "passive"))
      (node (ref "R24") (pin "2") (pinfunction "2_2") (pintype "passive"))
      (node (ref "U$4") (pin "P$21") (pinfunction "VADC2_P$21") (pintype "bidirectional"))
      (node (ref "U$4") (pin "P$30") (pinfunction "VADC_P$30") (pintype "bidirectional"))
      (node (ref "U$4") (pin "P$4") (pinfunction "VADC1_P$4") (pintype "bidirectional"))
    )
    (net (code "84") (name "VCCIO") (class "Default")
      (node (ref "C14") (pin "1") (pinfunction "1_1") (pintype "passive"))
      (node (ref "C15") (pin "1") (pinfunction "1_1") (pintype "passive"))
      (node (ref "C19") (pin "1") (pinfunction "1_1") (pintype "passive"))
      (node (ref "C32") (pin "1") (pinfunction "1_1") (pintype "passive"))
      (node (ref "JX1") (pin "P$21") (pinfunction "P$80_P$21") (pintype "bidirectional"))
      (node (ref "JX1") (pin "P$22") (pinfunction "P$79_P$22") (pintype "bidirectional"))
      (node (ref "JX1") (pin "P$23") (pinfunction "P$78_P$23") (pintype "bidirectional"))
      (node (ref "JX2") (pin "P$21") (pinfunction "P$80_P$21") (pintype "bidirectional"))
      (node (ref "JX2") (pin "P$22") (pinfunction "P$79_P$22") (pintype "bidirectional"))
      (node (ref "JX2") (pin "P$23") (pinfunction "P$78_P$23") (pintype "bidirectional"))
      (node (ref "PCA9306") (pin "2") (pinfunction "VREF1_2") (pintype "bidirectional"))
      (node (ref "R22") (pin "2") (pinfunction "2_2") (pintype "passive"))
      (node (ref "R31") (pin "1") (pinfunction "1_1") (pintype "passive"))
      (node (ref "RN7") (pin "1") (pinfunction "1_1") (pintype "passive"))
      (node (ref "RN7") (pin "2") (pinfunction "1_2") (pintype "passive"))
      (node (ref "U$11") (pin "1") (pinfunction "VOUT_1") (pintype "bidirectional"))
      (node (ref "U$11") (pin "2") (pinfunction "VO_SEN_2") (pintype "bidirectional"))
      (node (ref "U$18") (pin "P$6") (pinfunction "VDD_P$6") (pintype "bidirectional"))
      (node (ref "U$4") (pin "P$43") (pinfunction "VRESET_1_P$43") (pintype "bidirectional"))
      (node (ref "U$4") (pin "P$45") (pinfunction "VMEM_H_P$45") (pintype "bidirectional"))
    )
    (net (code "85") (name "VCCIO_EN") (class "Default")
      (node (ref "JX2") (pin "P$91") (pinfunction "P$10_P$91") (pintype "bidirectional"))
      (node (ref "R10") (pin "1") (pinfunction "1_1") (pintype "passive"))
      (node (ref "U$11") (pin "4") (pinfunction "EN_4") (pintype "bidirectional"))
      (node (ref "U$7") (pin "3") (pinfunction "D_3") (pintype "passive"))
      (node (ref "U$8") (pin "3") (pinfunction "C_3") (pintype "passive"))
    )
    (net (code "86") (name "VDDA") (class "Default")
      (node (ref "C5") (pin "1") (pinfunction "1_1") (pintype "passive"))
      (node (ref "F2") (pin "1") (pinfunction "1_1") (pintype "passive"))
      (node (ref "R25") (pin "2") (pinfunction "2_2") (pintype "passive"))
      (node (ref "R26") (pin "2") (pinfunction "2_2") (pintype "passive"))
      (node (ref "R27") (pin "2") (pinfunction "2_2") (pintype "passive"))
      (node (ref "R28") (pin "2") (pinfunction "2_2") (pintype "passive"))
      (node (ref "U$4") (pin "P$19") (pinfunction "VDDA1_P$19") (pintype "bidirectional"))
      (node (ref "U$4") (pin "P$8") (pinfunction "VDDA_P$8") (pintype "bidirectional"))
    )
    (net (code "87") (name "VDDD") (class "Default")
      (node (ref "C38") (pin "1") (pinfunction "1_1") (pintype "passive"))
      (node (ref "U$4") (pin "P$10") (pinfunction "VDDD_P$10") (pintype "bidirectional"))
      (node (ref "U$6") (pin "5") (pinfunction "VOUT_5") (pintype "bidirectional"))
    )
    (net (code "88") (name "VDDD1") (class "Default")
      (node (ref "C42") (pin "1") (pinfunction "1_1") (pintype "passive"))
      (node (ref "U$15") (pin "5") (pinfunction "VOUT_5") (pintype "bidirectional"))
      (node (ref "U$4") (pin "P$23") (pinfunction "VDDD1_P$23") (pintype "bidirectional"))
    )
    (net (code "89") (name "VDDO") (class "Default")
      (node (ref "C40") (pin "1") (pinfunction "1_1") (pintype "passive"))
      (node (ref "U$14") (pin "5") (pinfunction "VOUT_5") (pintype "bidirectional"))
      (node (ref "U$4") (pin "P$2") (pinfunction "VDDO_P$2") (pintype "bidirectional"))
    )
    (net (code "90") (name "VIN") (class "Default")
      (node (ref "K1") (pin "1") (pinfunction "1_1") (pintype "passive"))
      (node (ref "U$1") (pin "P$4") (pinfunction "2_P$4") (pintype "bidirectional"))
    )
    (net (code "91") (name "VPIX") (class "Default")
      (node (ref "C20") (pin "1") (pinfunction "1_1") (pintype "passive"))
      (node (ref "F1") (pin "1") (pinfunction "1_1") (pintype "passive"))
      (node (ref "R23") (pin "2") (pinfunction "2_2") (pintype "passive"))
      (node (ref "U$4") (pin "P$13") (pinfunction "VPIX_P$13") (pintype "bidirectional"))
    )
    (net (code "92") (name "unconnected-(J5-CEC-Pad13)") (class "Default")
      (node (ref "J5") (pin "13") (pinfunction "CEC_13") (pintype "bidirectional"))
    )
    (net (code "93") (name "unconnected-(J5-SCL-Pad15)") (class "Default")
      (node (ref "J5") (pin "15") (pinfunction "SCL_15") (pintype "bidirectional"))
    )
    (net (code "94") (name "unconnected-(J5-SDA-Pad16)") (class "Default")
      (node (ref "J5") (pin "16") (pinfunction "SDA_16") (pintype "bidirectional"))
    )
    (net (code "95") (name "unconnected-(J6-CEC-Pad13)") (class "Default")
      (node (ref "J6") (pin "13") (pinfunction "CEC_13") (pintype "bidirectional"))
    )
    (net (code "96") (name "unconnected-(JX1-P$1-PadP$100)") (class "Default")
      (node (ref "JX1") (pin "P$100") (pinfunction "P$1_P$100") (pintype "bidirectional"))
    )
    (net (code "97") (name "unconnected-(JX1-P$2-PadP$99)") (class "Default")
      (node (ref "JX1") (pin "P$99") (pinfunction "P$2_P$99") (pintype "bidirectional"))
    )
    (net (code "98") (name "unconnected-(JX1-P$3-PadP$98)") (class "Default")
      (node (ref "JX1") (pin "P$98") (pinfunction "P$3_P$98") (pintype "bidirectional"))
    )
    (net (code "99") (name "unconnected-(JX1-P$4-PadP$97)") (class "Default")
      (node (ref "JX1") (pin "P$97") (pinfunction "P$4_P$97") (pintype "bidirectional"))
    )
    (net (code "100") (name "unconnected-(JX1-P$6-PadP$95)") (class "Default")
      (node (ref "JX1") (pin "P$95") (pinfunction "P$6_P$95") (pintype "bidirectional"))
    )
    (net (code "101") (name "unconnected-(JX1-P$7-PadP$94)") (class "Default")
      (node (ref "JX1") (pin "P$94") (pinfunction "P$7_P$94") (pintype "bidirectional"))
    )
    (net (code "102") (name "unconnected-(JX1-P$8-PadP$93)") (class "Default")
      (node (ref "JX1") (pin "P$93") (pinfunction "P$8_P$93") (pintype "bidirectional"))
    )
    (net (code "103") (name "unconnected-(JX1-P$9-PadP$92)") (class "Default")
      (node (ref "JX1") (pin "P$92") (pinfunction "P$9_P$92") (pintype "bidirectional"))
    )
    (net (code "104") (name "unconnected-(JX1-P$10-PadP$91)") (class "Default")
      (node (ref "JX1") (pin "P$91") (pinfunction "P$10_P$91") (pintype "bidirectional"))
    )
    (net (code "105") (name "unconnected-(JX1-P$13-PadP$88)") (class "Default")
      (node (ref "JX1") (pin "P$88") (pinfunction "P$13_P$88") (pintype "bidirectional"))
    )
    (net (code "106") (name "unconnected-(JX1-P$20-PadP$81)") (class "Default")
      (node (ref "JX1") (pin "P$81") (pinfunction "P$20_P$81") (pintype "bidirectional"))
    )
    (net (code "107") (name "unconnected-(JX1-P$23-PadP$78)") (class "Default")
      (node (ref "JX1") (pin "P$78") (pinfunction "P$23_P$78") (pintype "bidirectional"))
    )
    (net (code "108") (name "unconnected-(JX1-P$25-PadP$76)") (class "Default")
      (node (ref "JX1") (pin "P$76") (pinfunction "P$25_P$76") (pintype "bidirectional"))
    )
    (net (code "109") (name "unconnected-(JX1-P$29-PadP$72)") (class "Default")
      (node (ref "JX1") (pin "P$72") (pinfunction "P$29_P$72") (pintype "bidirectional"))
    )
    (net (code "110") (name "unconnected-(JX1-P$31-PadP$70)") (class "Default")
      (node (ref "JX1") (pin "P$70") (pinfunction "P$31_P$70") (pintype "bidirectional"))
    )
    (net (code "111") (name "unconnected-(JX1-P$35-PadP$66)") (class "Default")
      (node (ref "JX1") (pin "P$66") (pinfunction "P$35_P$66") (pintype "bidirectional"))
    )
    (net (code "112") (name "unconnected-(JX1-P$37-PadP$64)") (class "Default")
      (node (ref "JX1") (pin "P$64") (pinfunction "P$37_P$64") (pintype "bidirectional"))
    )
    (net (code "113") (name "unconnected-(JX1-P$41-PadP$60)") (class "Default")
      (node (ref "JX1") (pin "P$60") (pinfunction "P$41_P$60") (pintype "bidirectional"))
    )
    (net (code "114") (name "unconnected-(JX1-P$43-PadP$58)") (class "Default")
      (node (ref "JX1") (pin "P$58") (pinfunction "P$43_P$58") (pintype "bidirectional"))
    )
    (net (code "115") (name "unconnected-(JX1-P$44-PadP$57)") (class "Default")
      (node (ref "JX1") (pin "P$57") (pinfunction "P$44_P$57") (pintype "bidirectional"))
    )
    (net (code "116") (name "unconnected-(JX1-P$47-PadP$54)") (class "Default")
      (node (ref "JX1") (pin "P$54") (pinfunction "P$47_P$54") (pintype "bidirectional"))
    )
    (net (code "117") (name "unconnected-(JX1-P$49-PadP$52)") (class "Default")
      (node (ref "JX1") (pin "P$52") (pinfunction "P$49_P$52") (pintype "bidirectional"))
    )
    (net (code "118") (name "unconnected-(JX1-P$53-PadP$48)") (class "Default")
      (node (ref "JX1") (pin "P$48") (pinfunction "P$53_P$48") (pintype "bidirectional"))
    )
    (net (code "119") (name "unconnected-(JX1-P$55-PadP$46)") (class "Default")
      (node (ref "JX1") (pin "P$46") (pinfunction "P$55_P$46") (pintype "bidirectional"))
    )
    (net (code "120") (name "unconnected-(JX1-P$61-PadP$40)") (class "Default")
      (node (ref "JX1") (pin "P$40") (pinfunction "P$61_P$40") (pintype "bidirectional"))
    )
    (net (code "121") (name "unconnected-(JX1-P$63-PadP$38)") (class "Default")
      (node (ref "JX1") (pin "P$38") (pinfunction "P$63_P$38") (pintype "bidirectional"))
    )
    (net (code "122") (name "unconnected-(JX1-P$67-PadP$34)") (class "Default")
      (node (ref "JX1") (pin "P$34") (pinfunction "P$67_P$34") (pintype "bidirectional"))
    )
    (net (code "123") (name "unconnected-(JX1-P$69-PadP$32)") (class "Default")
      (node (ref "JX1") (pin "P$32") (pinfunction "P$69_P$32") (pintype "bidirectional"))
    )
    (net (code "124") (name "unconnected-(JX1-P$73-PadP$28)") (class "Default")
      (node (ref "JX1") (pin "P$28") (pinfunction "P$73_P$28") (pintype "bidirectional"))
    )
    (net (code "125") (name "unconnected-(JX1-P$74-PadP$27)") (class "Default")
      (node (ref "JX1") (pin "P$27") (pinfunction "P$74_P$27") (pintype "bidirectional"))
    )
    (net (code "126") (name "unconnected-(JX1-P$75-PadP$26)") (class "Default")
      (node (ref "JX1") (pin "P$26") (pinfunction "P$75_P$26") (pintype "bidirectional"))
    )
    (net (code "127") (name "unconnected-(JX1-P$76-PadP$25)") (class "Default")
      (node (ref "JX1") (pin "P$25") (pinfunction "P$76_P$25") (pintype "bidirectional"))
    )
    (net (code "128") (name "unconnected-(JX1-P$81-PadP$20)") (class "Default")
      (node (ref "JX1") (pin "P$20") (pinfunction "P$81_P$20") (pintype "bidirectional"))
    )
    (net (code "129") (name "unconnected-(JX1-P$82-PadP$19)") (class "Default")
      (node (ref "JX1") (pin "P$19") (pinfunction "P$82_P$19") (pintype "bidirectional"))
    )
    (net (code "130") (name "unconnected-(JX1-P$83-PadP$18)") (class "Default")
      (node (ref "JX1") (pin "P$18") (pinfunction "P$83_P$18") (pintype "bidirectional"))
    )
    (net (code "131") (name "unconnected-(JX1-P$84-PadP$17)") (class "Default")
      (node (ref "JX1") (pin "P$17") (pinfunction "P$84_P$17") (pintype "bidirectional"))
    )
    (net (code "132") (name "unconnected-(JX1-P$87-PadP$14)") (class "Default")
      (node (ref "JX1") (pin "P$14") (pinfunction "P$87_P$14") (pintype "bidirectional"))
    )
    (net (code "133") (name "unconnected-(JX1-P$88-PadP$13)") (class "Default")
      (node (ref "JX1") (pin "P$13") (pinfunction "P$88_P$13") (pintype "bidirectional"))
    )
    (net (code "134") (name "unconnected-(JX1-P$89-PadP$12)") (class "Default")
      (node (ref "JX1") (pin "P$12") (pinfunction "P$89_P$12") (pintype "bidirectional"))
    )
    (net (code "135") (name "unconnected-(JX1-P$90-PadP$11)") (class "Default")
      (node (ref "JX1") (pin "P$11") (pinfunction "P$90_P$11") (pintype "bidirectional"))
    )
    (net (code "136") (name "unconnected-(JX1-P$91-PadP$10)") (class "Default")
      (node (ref "JX1") (pin "P$10") (pinfunction "P$91_P$10") (pintype "bidirectional"))
    )
    (net (code "137") (name "unconnected-(JX1-P$92-PadP$9)") (class "Default")
      (node (ref "JX1") (pin "P$9") (pinfunction "P$92_P$9") (pintype "bidirectional"))
    )
    (net (code "138") (name "unconnected-(JX1-P$93-PadP$8)") (class "Default")
      (node (ref "JX1") (pin "P$8") (pinfunction "P$93_P$8") (pintype "bidirectional"))
    )
    (net (code "139") (name "unconnected-(JX1-P$94-PadP$7)") (class "Default")
      (node (ref "JX1") (pin "P$7") (pinfunction "P$94_P$7") (pintype "bidirectional"))
    )
    (net (code "140") (name "unconnected-(JX2-P$1-PadP$100)") (class "Default")
      (node (ref "JX2") (pin "P$100") (pinfunction "P$1_P$100") (pintype "bidirectional"))
    )
    (net (code "141") (name "unconnected-(JX2-P$2-PadP$99)") (class "Default")
      (node (ref "JX2") (pin "P$99") (pinfunction "P$2_P$99") (pintype "bidirectional"))
    )
    (net (code "142") (name "unconnected-(JX2-P$3-PadP$98)") (class "Default")
      (node (ref "JX2") (pin "P$98") (pinfunction "P$3_P$98") (pintype "bidirectional"))
    )
    (net (code "143") (name "unconnected-(JX2-P$4-PadP$97)") (class "Default")
      (node (ref "JX2") (pin "P$97") (pinfunction "P$4_P$97") (pintype "bidirectional"))
    )
    (net (code "144") (name "unconnected-(JX2-P$5-PadP$96)") (class "Default")
      (node (ref "JX2") (pin "P$96") (pinfunction "P$5_P$96") (pintype "bidirectional"))
    )
    (net (code "145") (name "unconnected-(JX2-P$6-PadP$95)") (class "Default")
      (node (ref "JX2") (pin "P$95") (pinfunction "P$6_P$95") (pintype "bidirectional"))
    )
    (net (code "146") (name "unconnected-(JX2-P$7-PadP$94)") (class "Default")
      (node (ref "JX2") (pin "P$94") (pinfunction "P$7_P$94") (pintype "bidirectional"))
    )
    (net (code "147") (name "unconnected-(JX2-P$8-PadP$93)") (class "Default")
      (node (ref "JX2") (pin "P$93") (pinfunction "P$8_P$93") (pintype "bidirectional"))
    )
    (net (code "148") (name "unconnected-(JX2-P$9-PadP$92)") (class "Default")
      (node (ref "JX2") (pin "P$92") (pinfunction "P$9_P$92") (pintype "bidirectional"))
    )
    (net (code "149") (name "unconnected-(JX2-P$13-PadP$88)") (class "Default")
      (node (ref "JX2") (pin "P$88") (pinfunction "P$13_P$88") (pintype "bidirectional"))
    )
    (net (code "150") (name "unconnected-(JX2-P$14-PadP$87)") (class "Default")
      (node (ref "JX2") (pin "P$87") (pinfunction "P$14_P$87") (pintype "bidirectional"))
    )
    (net (code "151") (name "unconnected-(JX2-P$18-PadP$83)") (class "Default")
      (node (ref "JX2") (pin "P$83") (pinfunction "P$18_P$83") (pintype "bidirectional"))
    )
    (net (code "152") (name "unconnected-(JX2-P$20-PadP$81)") (class "Default")
      (node (ref "JX2") (pin "P$81") (pinfunction "P$20_P$81") (pintype "bidirectional"))
    )
    (net (code "153") (name "unconnected-(JX2-P$24-PadP$77)") (class "Default")
      (node (ref "JX2") (pin "P$77") (pinfunction "P$24_P$77") (pintype "bidirectional"))
    )
    (net (code "154") (name "unconnected-(JX2-P$26-PadP$75)") (class "Default")
      (node (ref "JX2") (pin "P$75") (pinfunction "P$26_P$75") (pintype "bidirectional"))
    )
    (net (code "155") (name "unconnected-(JX2-P$30-PadP$71)") (class "Default")
      (node (ref "JX2") (pin "P$71") (pinfunction "P$30_P$71") (pintype "bidirectional"))
    )
    (net (code "156") (name "unconnected-(JX2-P$32-PadP$69)") (class "Default")
      (node (ref "JX2") (pin "P$69") (pinfunction "P$32_P$69") (pintype "bidirectional"))
    )
    (net (code "157") (name "unconnected-(JX2-P$36-PadP$65)") (class "Default")
      (node (ref "JX2") (pin "P$65") (pinfunction "P$36_P$65") (pintype "bidirectional"))
    )
    (net (code "158") (name "unconnected-(JX2-P$38-PadP$63)") (class "Default")
      (node (ref "JX2") (pin "P$63") (pinfunction "P$38_P$63") (pintype "bidirectional"))
    )
    (net (code "159") (name "unconnected-(JX2-P$42-PadP$59)") (class "Default")
      (node (ref "JX2") (pin "P$59") (pinfunction "P$42_P$59") (pintype "bidirectional"))
    )
    (net (code "160") (name "unconnected-(JX2-P$44-PadP$57)") (class "Default")
      (node (ref "JX2") (pin "P$57") (pinfunction "P$44_P$57") (pintype "bidirectional"))
    )
    (net (code "161") (name "unconnected-(JX2-P$47-PadP$54)") (class "Default")
      (node (ref "JX2") (pin "P$54") (pinfunction "P$47_P$54") (pintype "bidirectional"))
    )
    (net (code "162") (name "unconnected-(JX2-P$48-PadP$53)") (class "Default")
      (node (ref "JX2") (pin "P$53") (pinfunction "P$48_P$53") (pintype "bidirectional"))
    )
    (net (code "163") (name "unconnected-(JX2-P$49-PadP$52)") (class "Default")
      (node (ref "JX2") (pin "P$52") (pinfunction "P$49_P$52") (pintype "bidirectional"))
    )
    (net (code "164") (name "unconnected-(JX2-P$50-PadP$51)") (class "Default")
      (node (ref "JX2") (pin "P$51") (pinfunction "P$50_P$51") (pintype "bidirectional"))
    )
    (net (code "165") (name "unconnected-(JX2-P$56-PadP$45)") (class "Default")
      (node (ref "JX2") (pin "P$45") (pinfunction "P$56_P$45") (pintype "bidirectional"))
    )
    (net (code "166") (name "unconnected-(JX2-P$62-PadP$39)") (class "Default")
      (node (ref "JX2") (pin "P$39") (pinfunction "P$62_P$39") (pintype "bidirectional"))
    )
    (net (code "167") (name "unconnected-(JX2-P$64-PadP$37)") (class "Default")
      (node (ref "JX2") (pin "P$37") (pinfunction "P$64_P$37") (pintype "bidirectional"))
    )
    (net (code "168") (name "unconnected-(JX2-P$68-PadP$33)") (class "Default")
      (node (ref "JX2") (pin "P$33") (pinfunction "P$68_P$33") (pintype "bidirectional"))
    )
    (net (code "169") (name "unconnected-(JX2-P$70-PadP$31)") (class "Default")
      (node (ref "JX2") (pin "P$31") (pinfunction "P$70_P$31") (pintype "bidirectional"))
    )
    (net (code "170") (name "unconnected-(JX2-P$74-PadP$27)") (class "Default")
      (node (ref "JX2") (pin "P$27") (pinfunction "P$74_P$27") (pintype "bidirectional"))
    )
    (net (code "171") (name "unconnected-(JX2-P$76-PadP$25)") (class "Default")
      (node (ref "JX2") (pin "P$25") (pinfunction "P$76_P$25") (pintype "bidirectional"))
    )
    (net (code "172") (name "unconnected-(JX2-P$81-PadP$20)") (class "Default")
      (node (ref "JX2") (pin "P$20") (pinfunction "P$81_P$20") (pintype "bidirectional"))
    )
    (net (code "173") (name "unconnected-(JX2-P$93-PadP$8)") (class "Default")
      (node (ref "JX2") (pin "P$8") (pinfunction "P$93_P$8") (pintype "bidirectional"))
    )
    (net (code "174") (name "unconnected-(JX2-P$94-PadP$7)") (class "Default")
      (node (ref "JX2") (pin "P$7") (pinfunction "P$94_P$7") (pintype "bidirectional"))
    )
    (net (code "175") (name "unconnected-(JX2-P$95-PadP$6)") (class "Default")
      (node (ref "JX2") (pin "P$6") (pinfunction "P$95_P$6") (pintype "bidirectional"))
    )
    (net (code "176") (name "unconnected-(JX2-P$96-PadP$5)") (class "Default")
      (node (ref "JX2") (pin "P$5") (pinfunction "P$96_P$5") (pintype "bidirectional"))
    )
    (net (code "177") (name "unconnected-(JX2-P$97-PadP$4)") (class "Default")
      (node (ref "JX2") (pin "P$4") (pinfunction "P$97_P$4") (pintype "bidirectional"))
    )
    (net (code "178") (name "unconnected-(JX2-P$98-PadP$3)") (class "Default")
      (node (ref "JX2") (pin "P$3") (pinfunction "P$98_P$3") (pintype "bidirectional"))
    )
    (net (code "179") (name "unconnected-(JX2-P$99-PadP$2)") (class "Default")
      (node (ref "JX2") (pin "P$2") (pinfunction "P$99_P$2") (pintype "bidirectional"))
    )
    (net (code "180") (name "unconnected-(JX2-P$100-PadP$1)") (class "Default")
      (node (ref "JX2") (pin "P$1") (pinfunction "P$100_P$1") (pintype "bidirectional"))
    )
    (net (code "181") (name "unconnected-(U$18-~{CLK}-PadP$5)") (class "Default")
      (node (ref "U$18") (pin "P$5") (pinfunction "~{CLK}_P$5") (pintype "bidirectional"))
    )
  )
)
